# zx80_SD_12_smd_build006_STM32.net
KiCad netlist of a schematic drawn in EAGLE
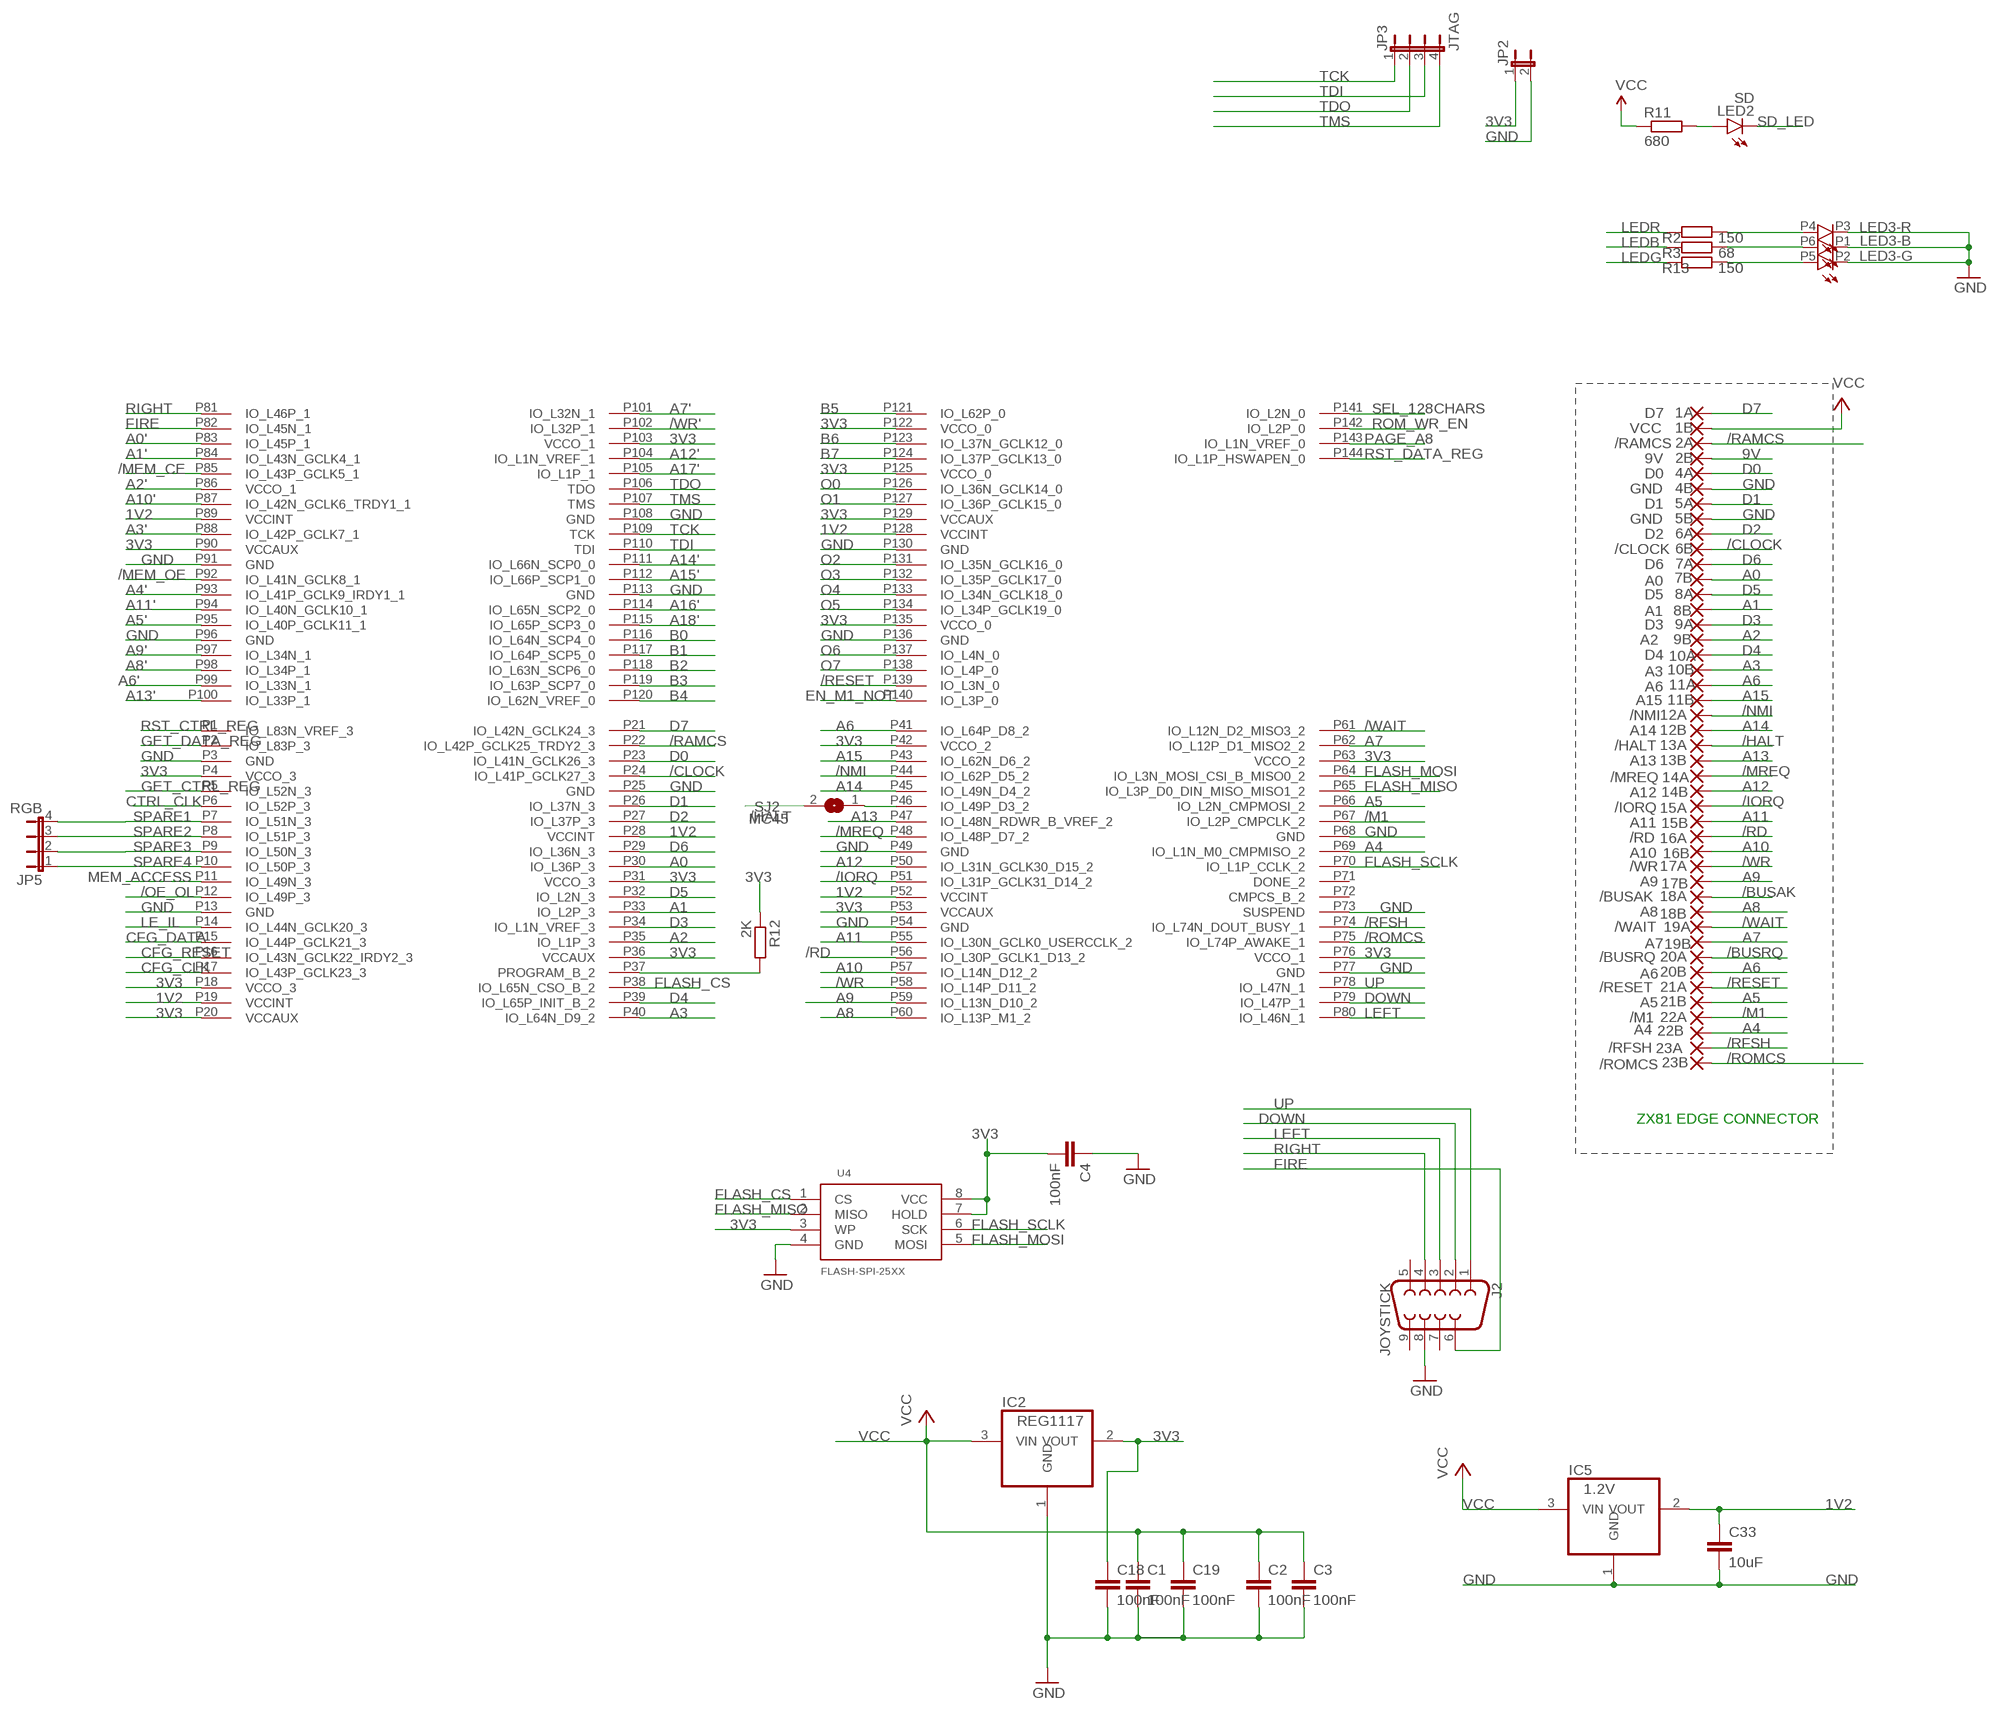
[diagram p0: schematic, sheet 1, part 1 of 2]
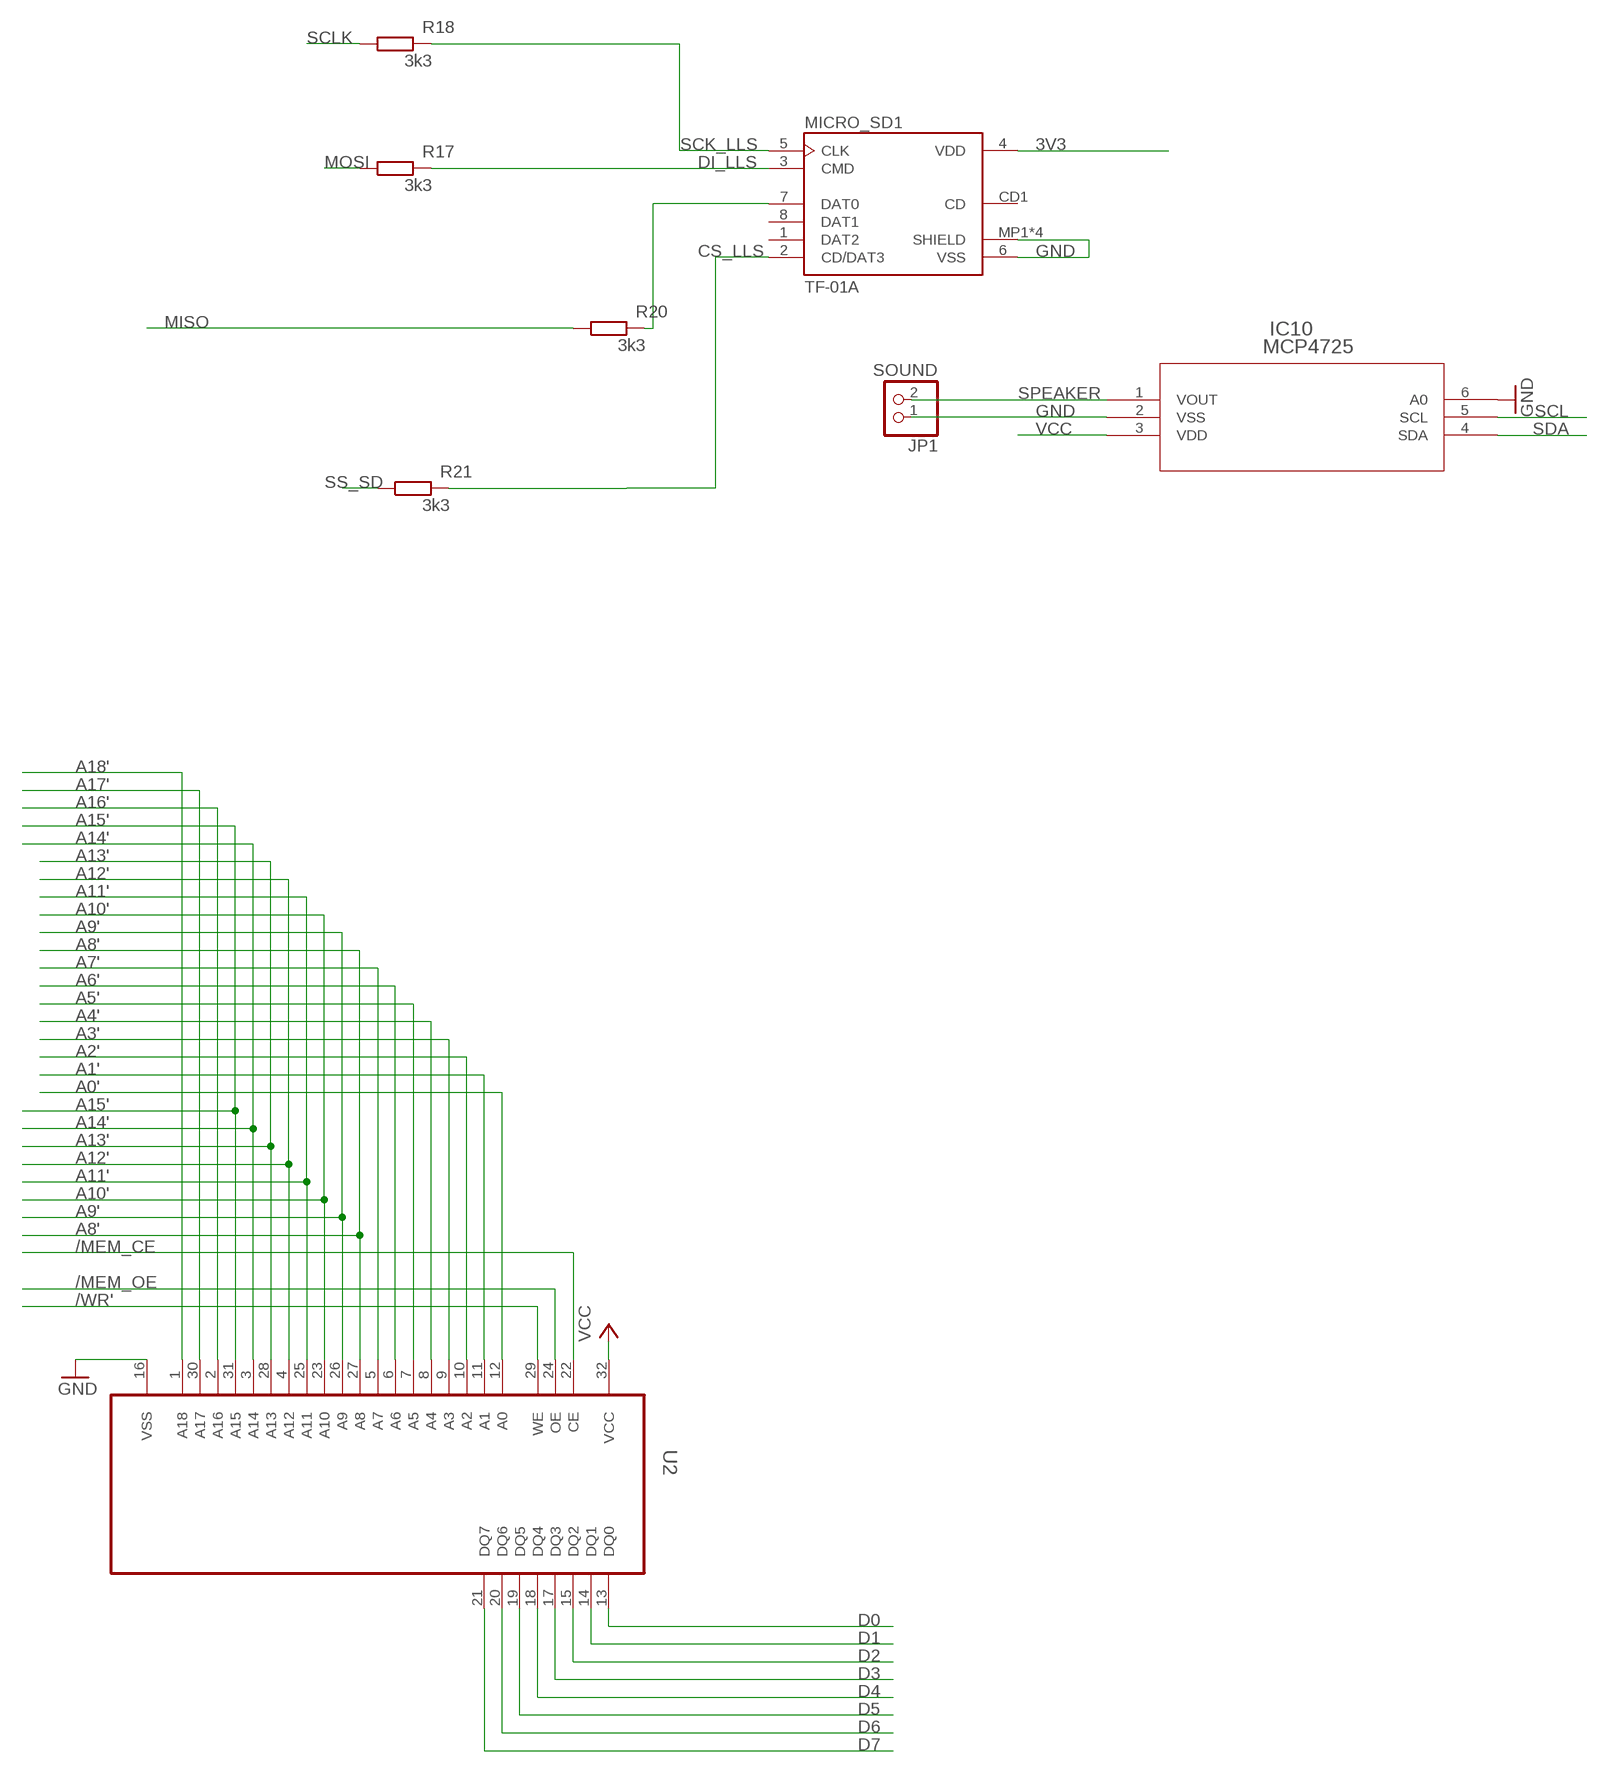
[diagram p1: schematic, sheet 1, part 2 of 2]
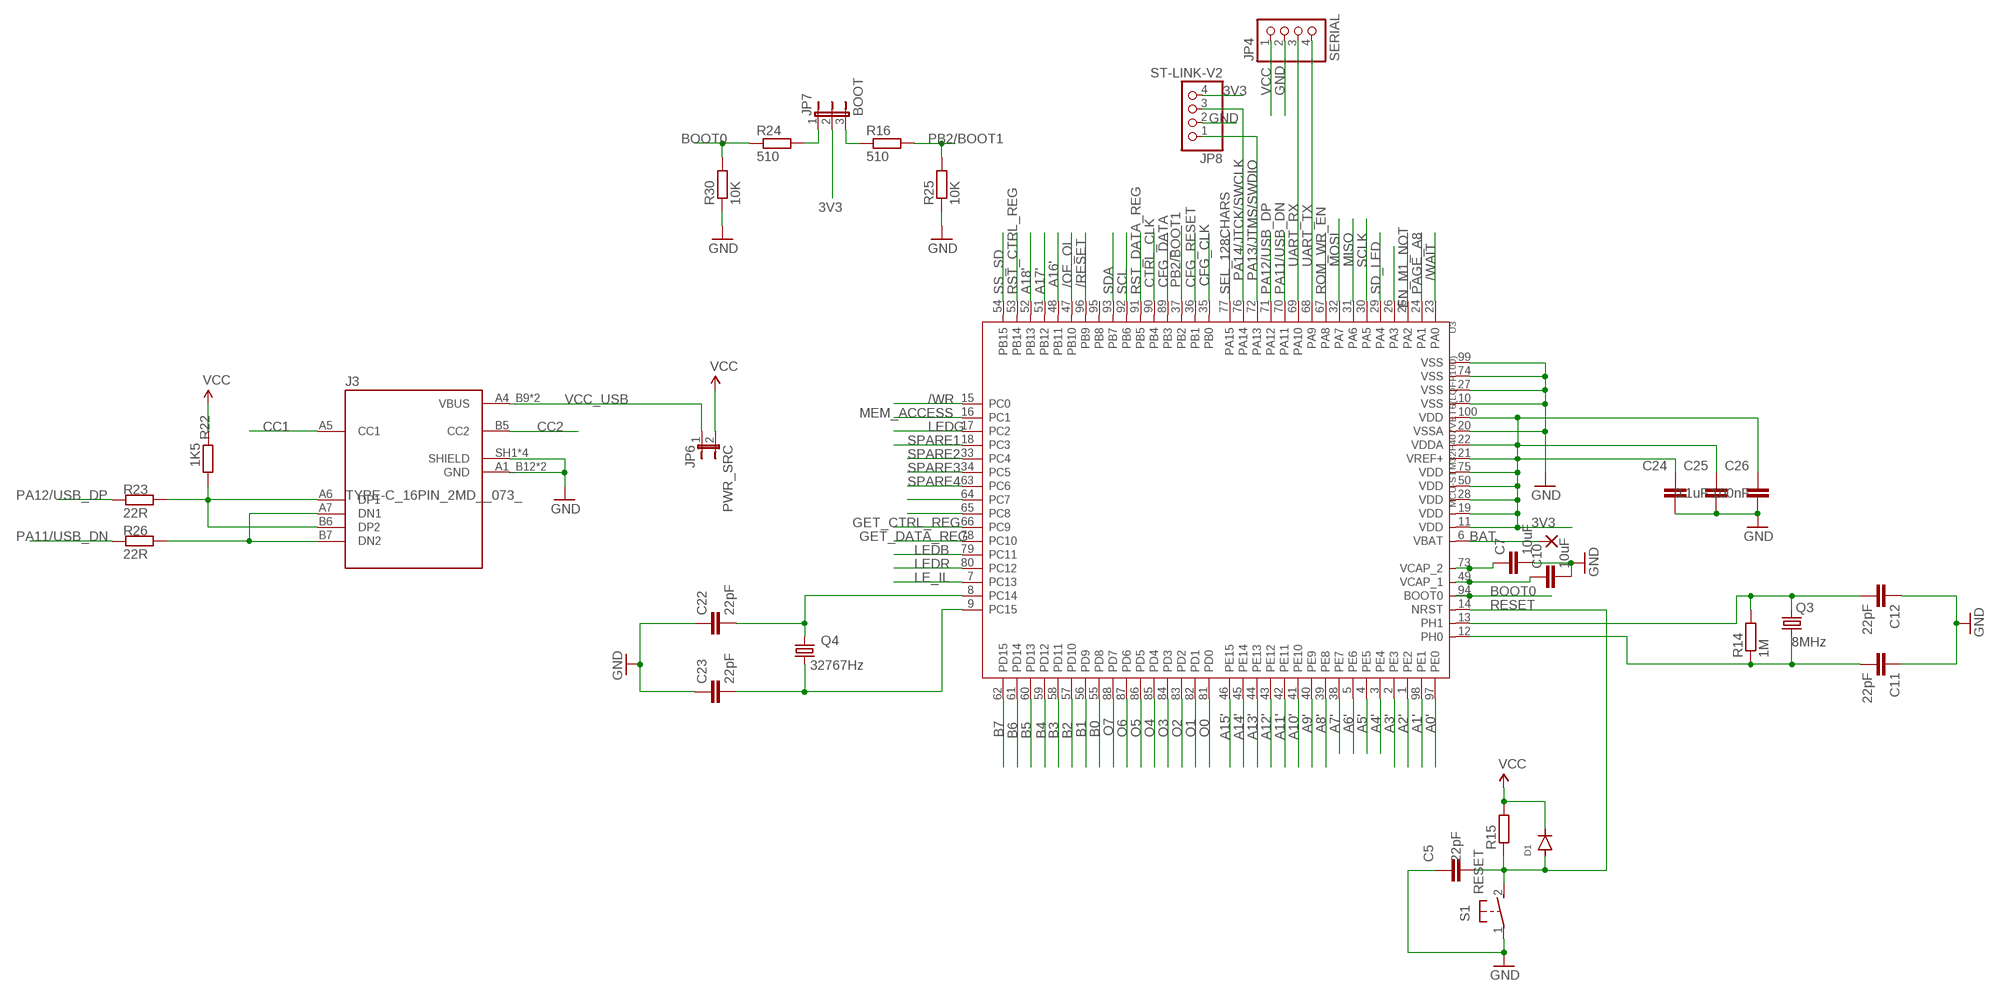
[diagram p2: schematic, sheet 2]

(export (version "E")
  (design (tool "Eeschema 10.0.6"))
  (components
    (comp (ref "BAT")
      (value "1,6/0,8")
      (footprint "eagle-import:1,6_0,8")
      (libsource (lib "eagle-import") (part "1,6/0,8"))
    )
    (comp (ref "C5")
      (value "22pF")
      (footprint "eagle-import:C0603")
      (libsource (lib "eagle-import") (part "rcl_334_C-EUC0603"))
    )
    (comp (ref "C7")
      (value "10uF")
      (footprint "eagle-import:C1206")
      (libsource (lib "eagle-import") (part "rcl_334_C-EUC1206"))
    )
    (comp (ref "C10")
      (value "10uF")
      (footprint "eagle-import:C1206")
      (libsource (lib "eagle-import") (part "rcl_334_C-EUC1206"))
    )
    (comp (ref "C11")
      (value "22pF")
      (footprint "eagle-import:C0603")
      (libsource (lib "eagle-import") (part "rcl_334_C-EUC0603"))
    )
    (comp (ref "C12")
      (value "22pF")
      (footprint "eagle-import:C0603")
      (libsource (lib "eagle-import") (part "rcl_334_C-EUC0603"))
    )
    (comp (ref "C22")
      (value "22pF")
      (footprint "eagle-import:C0603")
      (libsource (lib "eagle-import") (part "rcl_334_C-EUC0603"))
    )
    (comp (ref "C23")
      (value "22pF")
      (footprint "eagle-import:C0603")
      (libsource (lib "eagle-import") (part "rcl_334_C-EUC0603"))
    )
    (comp (ref "C24")
      (value "0.1uF")
      (footprint "eagle-import:C0603")
      (libsource (lib "eagle-import") (part "rcl_334_C-EUC0603"))
    )
    (comp (ref "C25")
      (value "0.1uF")
      (footprint "eagle-import:C0603")
      (libsource (lib "eagle-import") (part "rcl_334_C-EUC0603"))
    )
    (comp (ref "C26")
      (value "100nF")
      (footprint "eagle-import:C0603")
      (libsource (lib "eagle-import") (part "rcl_334_C-EUC0603"))
    )
    (comp (ref "D1")
      (value "DIODE-SOD123")
      (footprint "eagle-import:SOD123")
      (libsource (lib "eagle-import") (part "DIODE-SOD123"))
    )
    (comp (ref "J3")
      (value "TYPE-C_16PIN_2MD__073_")
      (footprint "eagle-import:SHOUHAN_TYPE-C_16PIN_2MD__073_")
      (fields (field (name "MF") "Shouhan") (field (name "MP") "TYPE-C 16PIN 2MD (073)"))
      (libsource (lib "eagle-import") (part "TYPE-C_16PIN_2MD__073_"))
    )
    (comp (ref "JP4")
      (value "SERIAL")
      (footprint "eagle-import:1X04")
      (libsource (lib "eagle-import") (part "PINHD-1X4"))
    )
    (comp (ref "JP6")
      (value "PWR_SRC")
      (footprint "eagle-import:HDRV2W64P254_2X1_300X350X838B")
      (libsource (lib "eagle-import") (part "JP1EJP13D"))
    )
    (comp (ref "JP7")
      (value "BOOT")
      (footprint "eagle-import:HDRV3W64P254_3X1_300X654X838B")
      (libsource (lib "eagle-import") (part "JP2EJP23D"))
    )
    (comp (ref "JP8")
      (value "ST-LINK-V2")
      (footprint "eagle-import:1X04")
      (libsource (lib "eagle-import") (part "PINHD-1X4"))
    )
    (comp (ref "Q3")
      (value "8MHz")
      (footprint "eagle-import:3.2X2.5_KX-7")
      (libsource (lib "eagle-import") (part "KX-7"))
    )
    (comp (ref "Q4")
      (value "32767Hz")
      (footprint "eagle-import:3.2X1.5")
      (libsource (lib "eagle-import") (part "KX-327-NHT"))
    )
    (comp (ref "R14")
      (value "1M")
      (footprint "eagle-import:R0603")
      (libsource (lib "eagle-import") (part "rcl_334_R-EU_R0603"))
    )
    (comp (ref "R15")
      (value "R-EU_R0603")
      (footprint "eagle-import:R0603")
      (libsource (lib "eagle-import") (part "rcl_334_R-EU_R0603"))
    )
    (comp (ref "R16")
      (value "510")
      (footprint "eagle-import:R0603")
      (libsource (lib "eagle-import") (part "rcl_334_R-EU_R0603"))
    )
    (comp (ref "R22")
      (value "1K5")
      (footprint "eagle-import:R0603")
      (libsource (lib "eagle-import") (part "R-EU_R0603"))
    )
    (comp (ref "R23")
      (value "22R")
      (footprint "eagle-import:R0603")
      (libsource (lib "eagle-import") (part "R-EU_R0603"))
    )
    (comp (ref "R24")
      (value "510")
      (footprint "eagle-import:R0603")
      (libsource (lib "eagle-import") (part "rcl_334_R-EU_R0603"))
    )
    (comp (ref "R25")
      (value "10K")
      (footprint "eagle-import:R0603")
      (libsource (lib "eagle-import") (part "rcl_334_R-EU_R0603"))
    )
    (comp (ref "R26")
      (value "22R")
      (footprint "eagle-import:R0603")
      (libsource (lib "eagle-import") (part "R-EU_R0603"))
    )
    (comp (ref "R30")
      (value "10K")
      (footprint "eagle-import:R0603")
      (libsource (lib "eagle-import") (part "rcl_334_R-EU_R0603"))
    )
    (comp (ref "S1")
      (value "RESET")
      (footprint "eagle-import:B3F-31XX")
      (fields (field (name "MPN") "B3F-3100"))
      (libsource (lib "eagle-import") (part "31-XX"))
    )
    (comp (ref "U3")
      (value "MCU-STM32F407VET6(LQFP100)")
      (footprint "eagle-import:LQFP100-0.5-13.8X13.8MM")
      (fields (field (name "MF") "STMicroelectronics") (field (name "MP") "STM32F407VET6"))
      (libsource (lib "eagle-import") (part "MCU-STM32F407VET6(LQFP100)"))
    )
    (comp (ref "1A")
      (value "D7")
      (footprint "eagle-import:EDGEPIN")
      (libsource (lib "eagle-import") (part "SMD2EDGEPIN"))
    )
    (comp (ref "1B")
      (value "VCC")
      (footprint "eagle-import:EDGEPIN")
      (libsource (lib "eagle-import") (part "SMD2EDGEPIN"))
    )
    (comp (ref "2A")
      (value "/RAMCS")
      (footprint "eagle-import:EDGEPIN")
      (libsource (lib "eagle-import") (part "SMD2EDGEPIN"))
    )
    (comp (ref "2B")
      (value "9V")
      (footprint "eagle-import:EDGEPIN")
      (libsource (lib "eagle-import") (part "SMD2EDGEPIN"))
    )
    (comp (ref "4A")
      (value "D0")
      (footprint "eagle-import:EDGEPIN")
      (libsource (lib "eagle-import") (part "SMD2EDGEPIN"))
    )
    (comp (ref "4B")
      (value "GND")
      (footprint "eagle-import:EDGEPIN")
      (libsource (lib "eagle-import") (part "SMD2EDGEPIN"))
    )
    (comp (ref "5A")
      (value "D1")
      (footprint "eagle-import:EDGEPIN")
      (libsource (lib "eagle-import") (part "SMD2EDGEPIN"))
    )
    (comp (ref "5B")
      (value "GND")
      (footprint "eagle-import:EDGEPIN")
      (libsource (lib "eagle-import") (part "SMD2EDGEPIN"))
    )
    (comp (ref "6A")
      (value "D2")
      (footprint "eagle-import:EDGEPIN")
      (libsource (lib "eagle-import") (part "SMD2EDGEPIN"))
    )
    (comp (ref "6B")
      (value "/CLOCK")
      (footprint "eagle-import:EDGEPIN")
      (libsource (lib "eagle-import") (part "SMD2EDGEPIN"))
    )
    (comp (ref "7A")
      (value "D6")
      (footprint "eagle-import:EDGEPIN")
      (libsource (lib "eagle-import") (part "SMD2EDGEPIN"))
    )
    (comp (ref "7B")
      (value "A0")
      (footprint "eagle-import:EDGEPIN")
      (libsource (lib "eagle-import") (part "SMD2EDGEPIN"))
    )
    (comp (ref "8A")
      (value "D5")
      (footprint "eagle-import:EDGEPIN")
      (libsource (lib "eagle-import") (part "SMD2EDGEPIN"))
    )
    (comp (ref "8B")
      (value "A1")
      (footprint "eagle-import:EDGEPIN")
      (libsource (lib "eagle-import") (part "SMD2EDGEPIN"))
    )
    (comp (ref "9A")
      (value "D3")
      (footprint "eagle-import:EDGEPIN")
      (libsource (lib "eagle-import") (part "SMD2EDGEPIN"))
    )
    (comp (ref "9B")
      (value "A2")
      (footprint "eagle-import:EDGEPIN")
      (libsource (lib "eagle-import") (part "SMD2EDGEPIN"))
    )
    (comp (ref "10A")
      (value "D4")
      (footprint "eagle-import:EDGEPIN")
      (libsource (lib "eagle-import") (part "SMD2EDGEPIN"))
    )
    (comp (ref "10B")
      (value "A3")
      (footprint "eagle-import:EDGEPIN")
      (libsource (lib "eagle-import") (part "SMD2EDGEPIN"))
    )
    (comp (ref "11A")
      (value "A6")
      (footprint "eagle-import:EDGEPIN")
      (libsource (lib "eagle-import") (part "SMD2EDGEPIN"))
    )
    (comp (ref "11B")
      (value "A15")
      (footprint "eagle-import:EDGEPIN")
      (libsource (lib "eagle-import") (part "SMD2EDGEPIN"))
    )
    (comp (ref "12A")
      (value "/NMI")
      (footprint "eagle-import:EDGEPIN")
      (libsource (lib "eagle-import") (part "SMD2EDGEPIN"))
    )
    (comp (ref "12B")
      (value "A14")
      (footprint "eagle-import:EDGEPIN")
      (libsource (lib "eagle-import") (part "SMD2EDGEPIN"))
    )
    (comp (ref "13A")
      (value "/HALT")
      (footprint "eagle-import:EDGEPIN")
      (libsource (lib "eagle-import") (part "SMD2EDGEPIN"))
    )
    (comp (ref "13B")
      (value "A13")
      (footprint "eagle-import:EDGEPIN")
      (libsource (lib "eagle-import") (part "SMD2EDGEPIN"))
    )
    (comp (ref "14A")
      (value "/MREQ")
      (footprint "eagle-import:EDGEPIN")
      (libsource (lib "eagle-import") (part "SMD2EDGEPIN"))
    )
    (comp (ref "14B")
      (value "A12")
      (footprint "eagle-import:EDGEPIN")
      (libsource (lib "eagle-import") (part "SMD2EDGEPIN"))
    )
    (comp (ref "15A")
      (value "/IORQ")
      (footprint "eagle-import:EDGEPIN")
      (libsource (lib "eagle-import") (part "SMD2EDGEPIN"))
    )
    (comp (ref "15B")
      (value "A11")
      (footprint "eagle-import:EDGEPIN")
      (libsource (lib "eagle-import") (part "SMD2EDGEPIN"))
    )
    (comp (ref "16A")
      (value "/RD")
      (footprint "eagle-import:EDGEPIN")
      (libsource (lib "eagle-import") (part "SMD2EDGEPIN"))
    )
    (comp (ref "16B")
      (value "A10")
      (footprint "eagle-import:EDGEPIN")
      (libsource (lib "eagle-import") (part "SMD2EDGEPIN"))
    )
    (comp (ref "17A")
      (value "/WR")
      (footprint "eagle-import:EDGEPIN")
      (libsource (lib "eagle-import") (part "SMD2EDGEPIN"))
    )
    (comp (ref "17B")
      (value "A9")
      (footprint "eagle-import:EDGEPIN")
      (libsource (lib "eagle-import") (part "SMD2EDGEPIN"))
    )
    (comp (ref "18A")
      (value "/BUSAK")
      (footprint "eagle-import:EDGEPIN")
      (libsource (lib "eagle-import") (part "SMD2EDGEPIN"))
    )
    (comp (ref "18B")
      (value "A8")
      (footprint "eagle-import:EDGEPIN")
      (libsource (lib "eagle-import") (part "SMD2EDGEPIN"))
    )
    (comp (ref "19A")
      (value "/WAIT")
      (footprint "eagle-import:EDGEPIN")
      (libsource (lib "eagle-import") (part "SMD2EDGEPIN"))
    )
    (comp (ref "19B")
      (value "A7")
      (footprint "eagle-import:EDGEPIN")
      (libsource (lib "eagle-import") (part "SMD2EDGEPIN"))
    )
    (comp (ref "20A")
      (value "/BUSRQ")
      (footprint "eagle-import:EDGEPIN")
      (libsource (lib "eagle-import") (part "SMD2EDGEPIN"))
    )
    (comp (ref "20B")
      (value "A6")
      (footprint "eagle-import:EDGEPIN")
      (libsource (lib "eagle-import") (part "SMD2EDGEPIN"))
    )
    (comp (ref "21A")
      (value "/RESET")
      (footprint "eagle-import:EDGEPIN")
      (libsource (lib "eagle-import") (part "SMD2EDGEPIN"))
    )
    (comp (ref "21B")
      (value "A5")
      (footprint "eagle-import:EDGEPIN")
      (libsource (lib "eagle-import") (part "SMD2EDGEPIN"))
    )
    (comp (ref "22A")
      (value "/M1")
      (footprint "eagle-import:EDGEPIN")
      (libsource (lib "eagle-import") (part "SMD2EDGEPIN"))
    )
    (comp (ref "22B")
      (value "A4")
      (footprint "eagle-import:EDGEPIN")
      (libsource (lib "eagle-import") (part "SMD2EDGEPIN"))
    )
    (comp (ref "23A")
      (value "/RFSH")
      (footprint "eagle-import:EDGEPIN")
      (libsource (lib "eagle-import") (part "SMD2EDGEPIN"))
    )
    (comp (ref "23B")
      (value "/ROMCS")
      (footprint "eagle-import:EDGEPIN")
      (libsource (lib "eagle-import") (part "SMD2EDGEPIN"))
    )
    (comp (ref "C1")
      (value "100nF")
      (footprint "eagle-import:C0603")
      (libsource (lib "eagle-import") (part "rcl_334_C-EUC0603"))
    )
    (comp (ref "C2")
      (value "100nF")
      (footprint "eagle-import:C0603")
      (libsource (lib "eagle-import") (part "rcl_334_C-EUC0603"))
    )
    (comp (ref "C3")
      (value "100nF")
      (footprint "eagle-import:C0603")
      (libsource (lib "eagle-import") (part "rcl_334_C-EUC0603"))
    )
    (comp (ref "C4")
      (value "100nF")
      (footprint "eagle-import:C0603K")
      (libsource (lib "eagle-import") (part "C-EUC0603K"))
    )
    (comp (ref "C18")
      (value "100nF")
      (footprint "eagle-import:C0603")
      (libsource (lib "eagle-import") (part "rcl_334_C-EUC0603"))
    )
    (comp (ref "C19")
      (value "100nF")
      (footprint "eagle-import:C0603")
      (libsource (lib "eagle-import") (part "rcl_334_C-EUC0603"))
    )
    (comp (ref "C33")
      (value "10uF")
      (footprint "eagle-import:C0603K")
      (libsource (lib "eagle-import") (part "C-EUC0603K"))
    )
    (comp (ref "IC2")
      (value "REG1117")
      (footprint "eagle-import:SOT223")
      (libsource (lib "eagle-import") (part "burr-brown_41243815_REG1117"))
    )
    (comp (ref "IC5")
      (value "1.2V")
      (footprint "eagle-import:SOT223")
      (fields (field (name "MPN") "REG1117"))
      (libsource (lib "eagle-import") (part "REG1117"))
    )
    (comp (ref "IC10")
      (value "MCP4725")
      (footprint "eagle-import:SOT-23-6_MC")
      (fields (field (name "MF") "Microchip") (field (name "MP") "MCP4725A2T-E/CH"))
      (libsource (lib "eagle-import") (part "MCP4725A2T-E/CH"))
    )
    (comp (ref "J2")
      (value "JOYSTICK")
      (footprint "eagle-import:DB9_MALE")
      (libsource (lib "eagle-import") (part "DB9MALE"))
    )
    (comp (ref "JP1")
      (value "SOUND")
      (footprint "eagle-import:1X02")
      (libsource (lib "eagle-import") (part "PINHD-1X2"))
    )
    (comp (ref "JP2")
      (value "JP1E")
      (footprint "eagle-import:JP1")
      (libsource (lib "eagle-import") (part "JP1E"))
    )
    (comp (ref "JP3")
      (value "JTAG")
      (footprint "eagle-import:JP4")
      (libsource (lib "eagle-import") (part "JP4E"))
    )
    (comp (ref "JP5")
      (value "RGB")
      (footprint "eagle-import:JP4")
      (libsource (lib "eagle-import") (part "JP4E"))
    )
    (comp (ref "LED2")
      (value "SD")
      (footprint "eagle-import:CHIPLED_0603")
      (libsource (lib "eagle-import") (part "LEDCHIPLED_0603"))
    )
    (comp (ref "LED3")
      (value "STATUS")
      (footprint "eagle-import:3535-PLCC6")
      (libsource (lib "eagle-import") (part "3535RGB3535RGB"))
    )
    (comp (ref "MICRO_SD1")
      (value "TF-01A")
      (footprint "eagle-import:TF-01A")
      (fields (field (name "MF") "HRO Electronics Co., Ltd."))
      (libsource (lib "eagle-import") (part "TF-01A"))
    )
    (comp (ref "R2")
      (value "150")
      (footprint "eagle-import:R0603")
      (libsource (lib "eagle-import") (part "rcl_334_R-EU_R0603"))
    )
    (comp (ref "R3")
      (value "68")
      (footprint "eagle-import:R0603")
      (libsource (lib "eagle-import") (part "rcl_334_R-EU_R0603"))
    )
    (comp (ref "R11")
      (value "680")
      (footprint "eagle-import:R0603")
      (libsource (lib "eagle-import") (part "R-EU_R0603"))
    )
    (comp (ref "R12")
      (value "2K")
      (footprint "eagle-import:R0603")
      (libsource (lib "eagle-import") (part "rcl_334_R-EU_R0603"))
    )
    (comp (ref "R13")
      (value "150")
      (footprint "eagle-import:R0603")
      (libsource (lib "eagle-import") (part "rcl_334_R-EU_R0603"))
    )
    (comp (ref "R17")
      (value "3k3")
      (footprint "eagle-import:R0603")
      (libsource (lib "eagle-import") (part "R-EU_R0603"))
    )
    (comp (ref "R18")
      (value "3k3")
      (footprint "eagle-import:R0603")
      (libsource (lib "eagle-import") (part "R-EU_R0603"))
    )
    (comp (ref "R20")
      (value "3k3")
      (footprint "eagle-import:R0603")
      (libsource (lib "eagle-import") (part "R-EU_R0603"))
    )
    (comp (ref "R21")
      (value "3k3")
      (footprint "eagle-import:R0603")
      (libsource (lib "eagle-import") (part "R-EU_R0603"))
    )
    (comp (ref "SJ2")
      (value "MC45")
      (footprint "eagle-import:SJ")
      (libsource (lib "eagle-import") (part "SJ"))
    )
    (comp (ref "U$1")
      (value "XC6SLX9-2TQG144C")
      (footprint "eagle-import:TQ144")
      (fields (field (name "MF") "Xilinx Inc."))
      (libsource (lib "eagle-import") (part "XC6SLX9-2TQG144C"))
    )
    (comp (ref "U2")
      (value "AS6C4008")
      (footprint "eagle-import:SOP32-5")
      (libsource (lib "eagle-import") (part "AS6C4008-55SINSOP5"))
    )
    (comp (ref "U4")
      (value "FLASH-SPI-25XX")
      (footprint "eagle-import:SO08-EIAJ")
      (libsource (lib "eagle-import") (part "FLASH-SPI-25XXSMD1"))
    )
  )
  (nets
    (net (code "1") (name "1V2") (class "Default")
      (node (ref "C33") (pin "1") (pinfunction "1_1") (pintype "passive"))
      (node (ref "IC5") (pin "2") (pinfunction "VOUT_2") (pintype "output"))
      (node (ref "U$1") (pin "P128") (pinfunction "VCCINT_P128") (pintype "bidirectional"))
      (node (ref "U$1") (pin "P19") (pinfunction "VCCINT_P19") (pintype "bidirectional"))
      (node (ref "U$1") (pin "P28") (pinfunction "VCCINT_P28") (pintype "bidirectional"))
      (node (ref "U$1") (pin "P52") (pinfunction "VCCINT_P52") (pintype "bidirectional"))
      (node (ref "U$1") (pin "P89") (pinfunction "VCCINT_P89") (pintype "bidirectional"))
    )
    (net (code "2") (name "3V3") (class "Default")
      (node (ref "C18") (pin "1") (pinfunction "1_1") (pintype "passive"))
      (node (ref "C24") (pin "1") (pinfunction "1_1") (pintype "passive"))
      (node (ref "C25") (pin "1") (pinfunction "1_1") (pintype "passive"))
      (node (ref "C26") (pin "1") (pinfunction "1_1") (pintype "passive"))
      (node (ref "C4") (pin "2") (pinfunction "2_2") (pintype "passive"))
      (node (ref "IC2") (pin "2") (pinfunction "VOUT_2") (pintype "output"))
      (node (ref "JP2") (pin "1") (pinfunction "1_1") (pintype "passive"))
      (node (ref "JP7") (pin "2") (pinfunction "2_2") (pintype "passive"))
      (node (ref "JP8") (pin "4") (pinfunction "4_4") (pintype "passive"))
      (node (ref "MICRO_SD1") (pin "4") (pinfunction "VDD_4") (pintype "power_in"))
      (node (ref "R12") (pin "1") (pinfunction "1_1") (pintype "passive"))
      (node (ref "U$1") (pin "P103") (pinfunction "VCCO_1_P103") (pintype "bidirectional"))
      (node (ref "U$1") (pin "P122") (pinfunction "VCCO_0_P122") (pintype "bidirectional"))
      (node (ref "U$1") (pin "P125") (pinfunction "VCCO_0_P125") (pintype "bidirectional"))
      (node (ref "U$1") (pin "P129") (pinfunction "VCCAUX_P129") (pintype "bidirectional"))
      (node (ref "U$1") (pin "P135") (pinfunction "VCCO_0_P135") (pintype "bidirectional"))
      (node (ref "U$1") (pin "P18") (pinfunction "VCCO_3_P18") (pintype "bidirectional"))
      (node (ref "U$1") (pin "P20") (pinfunction "VCCAUX_P20") (pintype "bidirectional"))
      (node (ref "U$1") (pin "P31") (pinfunction "VCCO_3_P31") (pintype "bidirectional"))
      (node (ref "U$1") (pin "P36") (pinfunction "VCCAUX_P36") (pintype "bidirectional"))
      (node (ref "U$1") (pin "P4") (pinfunction "VCCO_3_P4") (pintype "bidirectional"))
      (node (ref "U$1") (pin "P42") (pinfunction "VCCO_2_P42") (pintype "bidirectional"))
      (node (ref "U$1") (pin "P53") (pinfunction "VCCAUX_P53") (pintype "bidirectional"))
      (node (ref "U$1") (pin "P63") (pinfunction "VCCO_2_P63") (pintype "bidirectional"))
      (node (ref "U$1") (pin "P76") (pinfunction "VCCO_1_P76") (pintype "bidirectional"))
      (node (ref "U$1") (pin "P90") (pinfunction "VCCAUX_P90") (pintype "bidirectional"))
      (node (ref "U3") (pin "100") (pinfunction "VDD_100") (pintype "bidirectional"))
      (node (ref "U3") (pin "11") (pinfunction "VDD_11") (pintype "bidirectional"))
      (node (ref "U3") (pin "19") (pinfunction "VDD_19") (pintype "bidirectional"))
      (node (ref "U3") (pin "21") (pinfunction "VREF+_21") (pintype "bidirectional"))
      (node (ref "U3") (pin "22") (pinfunction "VDDA_22") (pintype "bidirectional"))
      (node (ref "U3") (pin "28") (pinfunction "VDD_28") (pintype "bidirectional"))
      (node (ref "U3") (pin "50") (pinfunction "VDD_50") (pintype "bidirectional"))
      (node (ref "U3") (pin "75") (pinfunction "VDD_75") (pintype "bidirectional"))
      (node (ref "U4") (pin "3") (pinfunction "WP_3") (pintype "bidirectional"))
      (node (ref "U4") (pin "7") (pinfunction "HOLD_7") (pintype "bidirectional"))
      (node (ref "U4") (pin "8") (pinfunction "VCC_8") (pintype "bidirectional"))
    )
    (net (code "3") (name "9V") (class "Default")
      (node (ref "2B") (pin "1") (pinfunction "P_1") (pintype "passive"))
    )
    (net (code "4") (name "A0") (class "Default")
      (node (ref "7B") (pin "1") (pinfunction "P_1") (pintype "passive"))
      (node (ref "U$1") (pin "P30") (pinfunction "IO_L36P_3_P30") (pintype "bidirectional"))
    )
    (net (code "5") (name "A0'") (class "Default")
      (node (ref "U$1") (pin "P83") (pinfunction "IO_L45P_1_P83") (pintype "bidirectional"))
      (node (ref "U2") (pin "12") (pinfunction "A0_12") (pintype "input"))
      (node (ref "U3") (pin "97") (pinfunction "PE0_97") (pintype "bidirectional"))
    )
    (net (code "6") (name "A1") (class "Default")
      (node (ref "8B") (pin "1") (pinfunction "P_1") (pintype "passive"))
      (node (ref "U$1") (pin "P33") (pinfunction "IO_L2P_3_P33") (pintype "bidirectional"))
    )
    (net (code "7") (name "A1'") (class "Default")
      (node (ref "U$1") (pin "P84") (pinfunction "IO_L43N_GCLK4_1_P84") (pintype "bidirectional"))
      (node (ref "U2") (pin "11") (pinfunction "A1_11") (pintype "input"))
      (node (ref "U3") (pin "98") (pinfunction "PE1_98") (pintype "bidirectional"))
    )
    (net (code "8") (name "A2") (class "Default")
      (node (ref "9B") (pin "1") (pinfunction "P_1") (pintype "passive"))
      (node (ref "U$1") (pin "P35") (pinfunction "IO_L1P_3_P35") (pintype "bidirectional"))
    )
    (net (code "9") (name "A2'") (class "Default")
      (node (ref "U$1") (pin "P86") (pinfunction "VCCO_1_P86") (pintype "bidirectional"))
      (node (ref "U2") (pin "10") (pinfunction "A2_10") (pintype "input"))
      (node (ref "U3") (pin "1") (pinfunction "PE2_1") (pintype "bidirectional"))
    )
    (net (code "10") (name "A3") (class "Default")
      (node (ref "10B") (pin "1") (pinfunction "P_1") (pintype "passive"))
      (node (ref "U$1") (pin "P40") (pinfunction "IO_L64N_D9_2_P40") (pintype "bidirectional"))
    )
    (net (code "11") (name "A3'") (class "Default")
      (node (ref "U$1") (pin "P88") (pinfunction "IO_L42P_GCLK7_1_P88") (pintype "bidirectional"))
      (node (ref "U2") (pin "9") (pinfunction "A3_9") (pintype "input"))
      (node (ref "U3") (pin "2") (pinfunction "PE3_2") (pintype "bidirectional"))
    )
    (net (code "12") (name "A4") (class "Default")
      (node (ref "22B") (pin "1") (pinfunction "P_1") (pintype "passive"))
      (node (ref "U$1") (pin "P69") (pinfunction "IO_L1N_M0_CMPMISO_2_P69") (pintype "bidirectional"))
    )
    (net (code "13") (name "A4'") (class "Default")
      (node (ref "U$1") (pin "P93") (pinfunction "IO_L41P_GCLK9_IRDY1_1_P93") (pintype "bidirectional"))
      (node (ref "U2") (pin "8") (pinfunction "A4_8") (pintype "input"))
      (node (ref "U3") (pin "3") (pinfunction "PE4_3") (pintype "bidirectional"))
    )
    (net (code "14") (name "A5") (class "Default")
      (node (ref "21B") (pin "1") (pinfunction "P_1") (pintype "passive"))
      (node (ref "U$1") (pin "P66") (pinfunction "IO_L2N_CMPMOSI_2_P66") (pintype "bidirectional"))
    )
    (net (code "15") (name "A5'") (class "Default")
      (node (ref "U$1") (pin "P95") (pinfunction "IO_L40P_GCLK11_1_P95") (pintype "bidirectional"))
      (node (ref "U2") (pin "7") (pinfunction "A5_7") (pintype "input"))
      (node (ref "U3") (pin "4") (pinfunction "PE5_4") (pintype "bidirectional"))
    )
    (net (code "16") (name "A6") (class "Default")
      (node (ref "11A") (pin "1") (pinfunction "P_1") (pintype "passive"))
      (node (ref "20B") (pin "1") (pinfunction "P_1") (pintype "passive"))
      (node (ref "U$1") (pin "P41") (pinfunction "IO_L64P_D8_2_P41") (pintype "bidirectional"))
    )
    (net (code "17") (name "A6'") (class "Default")
      (node (ref "U$1") (pin "P99") (pinfunction "IO_L33N_1_P99") (pintype "bidirectional"))
      (node (ref "U2") (pin "6") (pinfunction "A6_6") (pintype "input"))
      (node (ref "U3") (pin "5") (pinfunction "PE6_5") (pintype "bidirectional"))
    )
    (net (code "18") (name "A7") (class "Default")
      (node (ref "19B") (pin "1") (pinfunction "P_1") (pintype "passive"))
      (node (ref "U$1") (pin "P62") (pinfunction "IO_L12P_D1_MISO2_2_P62") (pintype "bidirectional"))
    )
    (net (code "19") (name "A7'") (class "Default")
      (node (ref "U$1") (pin "P101") (pinfunction "IO_L32N_1_P101") (pintype "bidirectional"))
      (node (ref "U2") (pin "5") (pinfunction "A7_5") (pintype "input"))
      (node (ref "U3") (pin "38") (pinfunction "PE7_38") (pintype "bidirectional"))
    )
    (net (code "20") (name "A8") (class "Default")
      (node (ref "18B") (pin "1") (pinfunction "P_1") (pintype "passive"))
      (node (ref "U$1") (pin "P60") (pinfunction "IO_L13P_M1_2_P60") (pintype "bidirectional"))
    )
    (net (code "21") (name "A8'") (class "Default")
      (node (ref "U$1") (pin "P98") (pinfunction "IO_L34P_1_P98") (pintype "bidirectional"))
      (node (ref "U2") (pin "27") (pinfunction "A8_27") (pintype "input"))
      (node (ref "U3") (pin "39") (pinfunction "PE8_39") (pintype "bidirectional"))
    )
    (net (code "22") (name "A9") (class "Default")
      (node (ref "17B") (pin "1") (pinfunction "P_1") (pintype "passive"))
      (node (ref "U$1") (pin "P59") (pinfunction "IO_L13N_D10_2_P59") (pintype "bidirectional"))
    )
    (net (code "23") (name "A9'") (class "Default")
      (node (ref "U$1") (pin "P97") (pinfunction "IO_L34N_1_P97") (pintype "bidirectional"))
      (node (ref "U2") (pin "26") (pinfunction "A9_26") (pintype "input"))
      (node (ref "U3") (pin "40") (pinfunction "PE9_40") (pintype "bidirectional"))
    )
    (net (code "24") (name "A10") (class "Default")
      (node (ref "16B") (pin "1") (pinfunction "P_1") (pintype "passive"))
      (node (ref "U$1") (pin "P57") (pinfunction "IO_L14N_D12_2_P57") (pintype "bidirectional"))
    )
    (net (code "25") (name "A10'") (class "Default")
      (node (ref "U$1") (pin "P87") (pinfunction "IO_L42N_GCLK6_TRDY1_1_P87") (pintype "bidirectional"))
      (node (ref "U2") (pin "23") (pinfunction "A10_23") (pintype "input"))
      (node (ref "U3") (pin "41") (pinfunction "PE10_41") (pintype "bidirectional"))
    )
    (net (code "26") (name "A11") (class "Default")
      (node (ref "15B") (pin "1") (pinfunction "P_1") (pintype "passive"))
      (node (ref "U$1") (pin "P55") (pinfunction "IO_L30N_GCLK0_USERCCLK_2_P55") (pintype "bidirectional"))
    )
    (net (code "27") (name "A11'") (class "Default")
      (node (ref "U$1") (pin "P94") (pinfunction "IO_L40N_GCLK10_1_P94") (pintype "bidirectional"))
      (node (ref "U2") (pin "25") (pinfunction "A11_25") (pintype "input"))
      (node (ref "U3") (pin "42") (pinfunction "PE11_42") (pintype "bidirectional"))
    )
    (net (code "28") (name "A12") (class "Default")
      (node (ref "14B") (pin "1") (pinfunction "P_1") (pintype "passive"))
      (node (ref "U$1") (pin "P50") (pinfunction "IO_L31N_GCLK30_D15_2_P50") (pintype "bidirectional"))
    )
    (net (code "29") (name "A12'") (class "Default")
      (node (ref "U$1") (pin "P104") (pinfunction "IO_L1N_VREF_1_P104") (pintype "bidirectional"))
      (node (ref "U2") (pin "4") (pinfunction "A12_4") (pintype "input"))
      (node (ref "U3") (pin "43") (pinfunction "PE12_43") (pintype "bidirectional"))
    )
    (net (code "30") (name "A13") (class "Default")
      (node (ref "13B") (pin "1") (pinfunction "P_1") (pintype "passive"))
      (node (ref "U$1") (pin "P47") (pinfunction "IO_L48N_RDWR_B_VREF_2_P47") (pintype "bidirectional"))
    )
    (net (code "31") (name "A13'") (class "Default")
      (node (ref "U$1") (pin "P100") (pinfunction "IO_L33P_1_P100") (pintype "bidirectional"))
      (node (ref "U2") (pin "28") (pinfunction "A13_28") (pintype "input"))
      (node (ref "U3") (pin "44") (pinfunction "PE13_44") (pintype "bidirectional"))
    )
    (net (code "32") (name "A14") (class "Default")
      (node (ref "12B") (pin "1") (pinfunction "P_1") (pintype "passive"))
      (node (ref "U$1") (pin "P45") (pinfunction "IO_L49N_D4_2_P45") (pintype "bidirectional"))
    )
    (net (code "33") (name "A14'") (class "Default")
      (node (ref "U$1") (pin "P111") (pinfunction "IO_L66N_SCP0_0_P111") (pintype "bidirectional"))
      (node (ref "U2") (pin "3") (pinfunction "A14_3") (pintype "input"))
      (node (ref "U3") (pin "45") (pinfunction "PE14_45") (pintype "bidirectional"))
    )
    (net (code "34") (name "A15") (class "Default")
      (node (ref "11B") (pin "1") (pinfunction "P_1") (pintype "passive"))
      (node (ref "U$1") (pin "P43") (pinfunction "IO_L62N_D6_2_P43") (pintype "bidirectional"))
    )
    (net (code "35") (name "A15'") (class "Default")
      (node (ref "U$1") (pin "P112") (pinfunction "IO_L66P_SCP1_0_P112") (pintype "bidirectional"))
      (node (ref "U2") (pin "31") (pinfunction "A15_31") (pintype "input"))
      (node (ref "U3") (pin "46") (pinfunction "PE15_46") (pintype "bidirectional"))
    )
    (net (code "36") (name "A16'") (class "Default")
      (node (ref "U$1") (pin "P114") (pinfunction "IO_L65N_SCP2_0_P114") (pintype "bidirectional"))
      (node (ref "U2") (pin "2") (pinfunction "A16_2") (pintype "input"))
      (node (ref "U3") (pin "48") (pinfunction "PB11_48") (pintype "bidirectional"))
    )
    (net (code "37") (name "A17'") (class "Default")
      (node (ref "U$1") (pin "P105") (pinfunction "IO_L1P_1_P105") (pintype "bidirectional"))
      (node (ref "U2") (pin "30") (pinfunction "A17_30") (pintype "input"))
      (node (ref "U3") (pin "51") (pinfunction "PB12_51") (pintype "bidirectional"))
    )
    (net (code "38") (name "A18'") (class "Default")
      (node (ref "U$1") (pin "P115") (pinfunction "IO_L65P_SCP3_0_P115") (pintype "bidirectional"))
      (node (ref "U2") (pin "1") (pinfunction "A18_1") (pintype "input"))
      (node (ref "U3") (pin "52") (pinfunction "PB13_52") (pintype "bidirectional"))
    )
    (net (code "39") (name "B0") (class "Default")
      (node (ref "U$1") (pin "P116") (pinfunction "IO_L64N_SCP4_0_P116") (pintype "bidirectional"))
      (node (ref "U3") (pin "55") (pinfunction "PD8_55") (pintype "bidirectional"))
    )
    (net (code "40") (name "B1") (class "Default")
      (node (ref "U$1") (pin "P117") (pinfunction "IO_L64P_SCP5_0_P117") (pintype "bidirectional"))
      (node (ref "U3") (pin "56") (pinfunction "PD9_56") (pintype "bidirectional"))
    )
    (net (code "41") (name "B2") (class "Default")
      (node (ref "U$1") (pin "P118") (pinfunction "IO_L63N_SCP6_0_P118") (pintype "bidirectional"))
      (node (ref "U3") (pin "57") (pinfunction "PD10_57") (pintype "bidirectional"))
    )
    (net (code "42") (name "B3") (class "Default")
      (node (ref "U$1") (pin "P119") (pinfunction "IO_L63P_SCP7_0_P119") (pintype "bidirectional"))
      (node (ref "U3") (pin "58") (pinfunction "PD11_58") (pintype "bidirectional"))
    )
    (net (code "43") (name "B4") (class "Default")
      (node (ref "U$1") (pin "P120") (pinfunction "IO_L62N_VREF_0_P120") (pintype "bidirectional"))
      (node (ref "U3") (pin "59") (pinfunction "PD12_59") (pintype "bidirectional"))
    )
    (net (code "44") (name "B5") (class "Default")
      (node (ref "U$1") (pin "P121") (pinfunction "IO_L62P_0_P121") (pintype "bidirectional"))
      (node (ref "U3") (pin "60") (pinfunction "PD13_60") (pintype "bidirectional"))
    )
    (net (code "45") (name "B6") (class "Default")
      (node (ref "U$1") (pin "P123") (pinfunction "IO_L37N_GCLK12_0_P123") (pintype "bidirectional"))
      (node (ref "U3") (pin "61") (pinfunction "PD14_61") (pintype "bidirectional"))
    )
    (net (code "46") (name "B7") (class "Default")
      (node (ref "U$1") (pin "P124") (pinfunction "IO_L37P_GCLK13_0_P124") (pintype "bidirectional"))
      (node (ref "U3") (pin "62") (pinfunction "PD15_62") (pintype "bidirectional"))
    )
    (net (code "47") (name "BAT") (class "Default")
      (node (ref "BAT") (pin "1") (pinfunction "P_1") (pintype "passive"))
      (node (ref "U3") (pin "6") (pinfunction "VBAT_6") (pintype "bidirectional"))
    )
    (net (code "48") (name "BOOT0") (class "Default")
      (node (ref "R24") (pin "1") (pinfunction "1_1") (pintype "passive"))
      (node (ref "R30") (pin "2") (pinfunction "2_2") (pintype "passive"))
      (node (ref "U3") (pin "94") (pinfunction "BOOT0_94") (pintype "bidirectional"))
    )
    (net (code "49") (name "CC1") (class "Default")
      (node (ref "J3") (pin "A5") (pinfunction "CC1_A5") (pintype "bidirectional"))
    )
    (net (code "50") (name "CC2") (class "Default")
      (node (ref "J3") (pin "B5") (pinfunction "CC2_B5") (pintype "bidirectional"))
    )
    (net (code "51") (name "CFG_CLK") (class "Default")
      (node (ref "U$1") (pin "P17") (pinfunction "IO_L43P_GCLK23_3_P17") (pintype "bidirectional"))
      (node (ref "U3") (pin "35") (pinfunction "PB0_35") (pintype "bidirectional"))
    )
    (net (code "52") (name "CFG_DATA") (class "Default")
      (node (ref "U$1") (pin "P15") (pinfunction "IO_L44P_GCLK21_3_P15") (pintype "bidirectional"))
      (node (ref "U3") (pin "89") (pinfunction "PB3_89") (pintype "bidirectional"))
    )
    (net (code "53") (name "CFG_RESET") (class "Default")
      (node (ref "U$1") (pin "P16") (pinfunction "IO_L43N_GCLK22_IRDY2_3_P16") (pintype "bidirectional"))
      (node (ref "U3") (pin "36") (pinfunction "PB1_36") (pintype "bidirectional"))
    )
    (net (code "54") (name "CS_LLS") (class "Default")
      (node (ref "MICRO_SD1") (pin "2") (pinfunction "CD/DAT3_2") (pintype "bidirectional"))
      (node (ref "R21") (pin "2") (pinfunction "2_2") (pintype "passive"))
    )
    (net (code "55") (name "CTRL_CLK") (class "Default")
      (node (ref "U$1") (pin "P6") (pinfunction "IO_L52P_3_P6") (pintype "bidirectional"))
      (node (ref "U3") (pin "90") (pinfunction "PB4_90") (pintype "bidirectional"))
    )
    (net (code "56") (name "D0") (class "Default")
      (node (ref "4A") (pin "1") (pinfunction "P_1") (pintype "passive"))
      (node (ref "U$1") (pin "P23") (pinfunction "IO_L41N_GCLK26_3_P23") (pintype "bidirectional"))
      (node (ref "U2") (pin "13") (pinfunction "DQ0_13") (pintype "output"))
    )
    (net (code "57") (name "D1") (class "Default")
      (node (ref "5A") (pin "1") (pinfunction "P_1") (pintype "passive"))
      (node (ref "U$1") (pin "P26") (pinfunction "IO_L37N_3_P26") (pintype "bidirectional"))
      (node (ref "U2") (pin "14") (pinfunction "DQ1_14") (pintype "output"))
    )
    (net (code "58") (name "D2") (class "Default")
      (node (ref "6A") (pin "1") (pinfunction "P_1") (pintype "passive"))
      (node (ref "U$1") (pin "P27") (pinfunction "IO_L37P_3_P27") (pintype "bidirectional"))
      (node (ref "U2") (pin "15") (pinfunction "DQ2_15") (pintype "output"))
    )
    (net (code "59") (name "D3") (class "Default")
      (node (ref "9A") (pin "1") (pinfunction "P_1") (pintype "passive"))
      (node (ref "U$1") (pin "P34") (pinfunction "IO_L1N_VREF_3_P34") (pintype "bidirectional"))
      (node (ref "U2") (pin "17") (pinfunction "DQ3_17") (pintype "output"))
    )
    (net (code "60") (name "D4") (class "Default")
      (node (ref "10A") (pin "1") (pinfunction "P_1") (pintype "passive"))
      (node (ref "U$1") (pin "P39") (pinfunction "IO_L65P_INIT_B_2_P39") (pintype "bidirectional"))
      (node (ref "U2") (pin "18") (pinfunction "DQ4_18") (pintype "output"))
    )
    (net (code "61") (name "D5") (class "Default")
      (node (ref "8A") (pin "1") (pinfunction "P_1") (pintype "passive"))
      (node (ref "U$1") (pin "P32") (pinfunction "IO_L2N_3_P32") (pintype "bidirectional"))
      (node (ref "U2") (pin "19") (pinfunction "DQ5_19") (pintype "output"))
    )
    (net (code "62") (name "D6") (class "Default")
      (node (ref "7A") (pin "1") (pinfunction "P_1") (pintype "passive"))
      (node (ref "U$1") (pin "P29") (pinfunction "IO_L36N_3_P29") (pintype "bidirectional"))
      (node (ref "U2") (pin "20") (pinfunction "DQ6_20") (pintype "output"))
    )
    (net (code "63") (name "D7") (class "Default")
      (node (ref "1A") (pin "1") (pinfunction "P_1") (pintype "passive"))
      (node (ref "U$1") (pin "P21") (pinfunction "IO_L42N_GCLK24_3_P21") (pintype "bidirectional"))
      (node (ref "U2") (pin "21") (pinfunction "DQ7_21") (pintype "output"))
    )
    (net (code "64") (name "DI_LLS") (class "Default")
      (node (ref "MICRO_SD1") (pin "3") (pinfunction "CMD_3") (pintype "bidirectional"))
      (node (ref "R17") (pin "2") (pinfunction "2_2") (pintype "passive"))
    )
    (net (code "65") (name "DOWN") (class "Default")
      (node (ref "J2") (pin "2") (pinfunction "2_2") (pintype "passive"))
      (node (ref "U$1") (pin "P79") (pinfunction "IO_L47P_1_P79") (pintype "bidirectional"))
    )
    (net (code "66") (name "EN_M1_NOT") (class "Default")
      (node (ref "U$1") (pin "P140") (pinfunction "IO_L3P_0_P140") (pintype "bidirectional"))
      (node (ref "U3") (pin "25") (pinfunction "PA2_25") (pintype "bidirectional"))
    )
    (net (code "67") (name "FIRE") (class "Default")
      (node (ref "J2") (pin "6") (pinfunction "6_6") (pintype "passive"))
      (node (ref "U$1") (pin "P82") (pinfunction "IO_L45N_1_P82") (pintype "bidirectional"))
    )
    (net (code "68") (name "FLASH_CS") (class "Default")
      (node (ref "U$1") (pin "P38") (pinfunction "IO_L65N_CSO_B_2_P38") (pintype "bidirectional"))
      (node (ref "U4") (pin "1") (pinfunction "CS_1") (pintype "bidirectional"))
    )
    (net (code "69") (name "FLASH_MISO") (class "Default")
      (node (ref "U$1") (pin "P65") (pinfunction "IO_L3P_D0_DIN_MISO_MISO1_2_P65") (pintype "bidirectional"))
      (node (ref "U4") (pin "2") (pinfunction "MISO_2") (pintype "bidirectional"))
    )
    (net (code "70") (name "FLASH_MOSI") (class "Default")
      (node (ref "U$1") (pin "P64") (pinfunction "IO_L3N_MOSI_CSI_B_MISO0_2_P64") (pintype "bidirectional"))
      (node (ref "U4") (pin "5") (pinfunction "MOSI_5") (pintype "bidirectional"))
    )
    (net (code "71") (name "FLASH_SCLK") (class "Default")
      (node (ref "U$1") (pin "P70") (pinfunction "IO_L1P_CCLK_2_P70") (pintype "bidirectional"))
      (node (ref "U4") (pin "6") (pinfunction "SCK_6") (pintype "bidirectional"))
    )
    (net (code "72") (name "GET_CTRL_REG") (class "Default")
      (node (ref "U$1") (pin "P5") (pinfunction "IO_L52N_3_P5") (pintype "bidirectional"))
      (node (ref "U3") (pin "66") (pinfunction "PC9_66") (pintype "bidirectional"))
    )
    (net (code "73") (name "GET_DATA_REG") (class "Default")
      (node (ref "U$1") (pin "P2") (pinfunction "IO_L83P_3_P2") (pintype "bidirectional"))
      (node (ref "U3") (pin "78") (pinfunction "PC10_78") (pintype "bidirectional"))
    )
    (net (code "74") (name "GND") (class "Default")
      (node (ref "4B") (pin "1") (pinfunction "P_1") (pintype "passive"))
      (node (ref "5B") (pin "1") (pinfunction "P_1") (pintype "passive"))
      (node (ref "C1") (pin "2") (pinfunction "2_2") (pintype "passive"))
      (node (ref "C10") (pin "2") (pinfunction "2_2") (pintype "passive"))
      (node (ref "C11") (pin "1") (pinfunction "1_1") (pintype "passive"))
      (node (ref "C12") (pin "1") (pinfunction "1_1") (pintype "passive"))
      (node (ref "C18") (pin "2") (pinfunction "2_2") (pintype "passive"))
      (node (ref "C19") (pin "2") (pinfunction "2_2") (pintype "passive"))
      (node (ref "C2") (pin "2") (pinfunction "2_2") (pintype "passive"))
      (node (ref "C22") (pin "1") (pinfunction "1_1") (pintype "passive"))
      (node (ref "C23") (pin "1") (pinfunction "1_1") (pintype "passive"))
      (node (ref "C24") (pin "2") (pinfunction "2_2") (pintype "passive"))
      (node (ref "C25") (pin "2") (pinfunction "2_2") (pintype "passive"))
      (node (ref "C26") (pin "2") (pinfunction "2_2") (pintype "passive"))
      (node (ref "C3") (pin "2") (pinfunction "2_2") (pintype "passive"))
      (node (ref "C33") (pin "2") (pinfunction "2_2") (pintype "passive"))
      (node (ref "C4") (pin "1") (pinfunction "1_1") (pintype "passive"))
      (node (ref "C5") (pin "1") (pinfunction "1_1") (pintype "passive"))
      (node (ref "C7") (pin "2") (pinfunction "2_2") (pintype "passive"))
      (node (ref "IC10") (pin "2") (pinfunction "VSS_2") (pintype "passive"))
      (node (ref "IC10") (pin "6") (pinfunction "A0_6") (pintype "passive"))
      (node (ref "IC2") (pin "1") (pinfunction "GND_1") (pintype "power_in"))
      (node (ref "IC5") (pin "1") (pinfunction "GND_1") (pintype "power_in"))
      (node (ref "J2") (pin "8") (pinfunction "8_8") (pintype "passive"))
      (node (ref "J3") (pin "A1_B12") (pinfunction "GND_A1_B12") (pintype "power_in"))
      (node (ref "J3") (pin "B1_A12") (pinfunction "GND_B1_A12") (pintype "power_in"))
      (node (ref "J3") (pin "SH1") (pinfunction "SHIELD_SH1") (pintype "passive"))
      (node (ref "J3") (pin "SH2") (pinfunction "SHIELD_SH2") (pintype "passive"))
      (node (ref "J3") (pin "SH3") (pinfunction "SHIELD_SH3") (pintype "passive"))
      (node (ref "J3") (pin "SH4") (pinfunction "SHIELD_SH4") (pintype "passive"))
      (node (ref "JP1") (pin "1") (pinfunction "1_1") (pintype "passive"))
      (node (ref "JP2") (pin "2") (pinfunction "2_2") (pintype "passive"))
      (node (ref "JP4") (pin "2") (pinfunction "2_2") (pintype "passive"))
      (node (ref "JP8") (pin "2") (pinfunction "2_2") (pintype "passive"))
      (node (ref "LED3") (pin "P1") (pinfunction "C_P1") (pintype "passive"))
      (node (ref "LED3") (pin "P2") (pinfunction "C_P2") (pintype "passive"))
      (node (ref "LED3") (pin "P3") (pinfunction "C_P3") (pintype "passive"))
      (node (ref "MICRO_SD1") (pin "6") (pinfunction "VSS_6") (pintype "power_in"))
      (node (ref "MICRO_SD1") (pin "MP1") (pinfunction "SHIELD_MP1") (pintype "power_in"))
      (node (ref "MICRO_SD1") (pin "MP2") (pinfunction "SHIELD_MP2") (pintype "power_in"))
      (node (ref "MICRO_SD1") (pin "MP3") (pinfunction "SHIELD_MP3") (pintype "power_in"))
      (node (ref "MICRO_SD1") (pin "MP4") (pinfunction "SHIELD_MP4") (pintype "power_in"))
      (node (ref "R25") (pin "1") (pinfunction "1_1") (pintype "passive"))
      (node (ref "R30") (pin "1") (pinfunction "1_1") (pintype "passive"))
      (node (ref "S1") (pin "1") (pinfunction "P_1") (pintype "passive"))
      (node (ref "U$1") (pin "P108") (pinfunction "GND_P108") (pintype "bidirectional"))
      (node (ref "U$1") (pin "P113") (pinfunction "GND_P113") (pintype "bidirectional"))
      (node (ref "U$1") (pin "P13") (pinfunction "GND_P13") (pintype "bidirectional"))
      (node (ref "U$1") (pin "P130") (pinfunction "GND_P130") (pintype "bidirectional"))
      (node (ref "U$1") (pin "P136") (pinfunction "GND_P136") (pintype "bidirectional"))
      (node (ref "U$1") (pin "P25") (pinfunction "GND_P25") (pintype "bidirectional"))
      (node (ref "U$1") (pin "P3") (pinfunction "GND_P3") (pintype "bidirectional"))
      (node (ref "U$1") (pin "P49") (pinfunction "GND_P49") (pintype "bidirectional"))
      (node (ref "U$1") (pin "P54") (pinfunction "GND_P54") (pintype "bidirectional"))
      (node (ref "U$1") (pin "P68") (pinfunction "GND_P68") (pintype "bidirectional"))
      (node (ref "U$1") (pin "P73") (pinfunction "SUSPEND_P73") (pintype "bidirectional"))
      (node (ref "U$1") (pin "P77") (pinfunction "GND_P77") (pintype "bidirectional"))
      (node (ref "U$1") (pin "P91") (pinfunction "GND_P91") (pintype "bidirectional"))
      (node (ref "U$1") (pin "P96") (pinfunction "GND_P96") (pintype "bidirectional"))
      (node (ref "U2") (pin "16") (pinfunction "VSS_16") (pintype "output"))
      (node (ref "U3") (pin "10") (pinfunction "VSS_10") (pintype "bidirectional"))
      (node (ref "U3") (pin "20") (pinfunction "VSSA_20") (pintype "bidirectional"))
      (node (ref "U3") (pin "27") (pinfunction "VSS_27") (pintype "bidirectional"))
      (node (ref "U3") (pin "74") (pinfunction "VSS_74") (pintype "bidirectional"))
      (node (ref "U3") (pin "99") (pinfunction "VSS_99") (pintype "bidirectional"))
      (node (ref "U4") (pin "4") (pinfunction "GND_4") (pintype "bidirectional"))
    )
    (net (code "75") (name "LEDB") (class "Default")
      (node (ref "R3") (pin "1") (pinfunction "1_1") (pintype "passive"))
      (node (ref "U3") (pin "79") (pinfunction "PC11_79") (pintype "bidirectional"))
    )
    (net (code "76") (name "LEDG") (class "Default")
      (node (ref "R13") (pin "1") (pinfunction "1_1") (pintype "passive"))
      (node (ref "U3") (pin "17") (pinfunction "PC2_17") (pintype "bidirectional"))
    )
    (net (code "77") (name "LEDR") (class "Default")
      (node (ref "R2") (pin "1") (pinfunction "1_1") (pintype "passive"))
      (node (ref "U3") (pin "80") (pinfunction "PC12_80") (pintype "bidirectional"))
    )
    (net (code "78") (name "LEFT") (class "Default")
      (node (ref "J2") (pin "3") (pinfunction "3_3") (pintype "passive"))
      (node (ref "U$1") (pin "P80") (pinfunction "IO_L46N_1_P80") (pintype "bidirectional"))
    )
    (net (code "79") (name "LE_IL") (class "Default")
      (node (ref "U$1") (pin "P14") (pinfunction "IO_L44N_GCLK20_3_P14") (pintype "bidirectional"))
      (node (ref "U3") (pin "7") (pinfunction "PC13_7") (pintype "bidirectional"))
    )
    (net (code "80") (name "MEM_ACCESS") (class "Default")
      (node (ref "U$1") (pin "P11") (pinfunction "IO_L49N_3_P11") (pintype "bidirectional"))
      (node (ref "U3") (pin "16") (pinfunction "PC1_16") (pintype "bidirectional"))
    )
    (net (code "81") (name "MISO") (class "Default")
      (node (ref "R20") (pin "1") (pinfunction "1_1") (pintype "passive"))
      (node (ref "U3") (pin "31") (pinfunction "PA6_31") (pintype "bidirectional"))
    )
    (net (code "82") (name "MOSI") (class "Default")
      (node (ref "R17") (pin "1") (pinfunction "1_1") (pintype "passive"))
      (node (ref "U3") (pin "32") (pinfunction "PA7_32") (pintype "bidirectional"))
    )
    (net (code "83") (name "Net-(J3-DN1)") (class "Default")
      (node (ref "J3") (pin "A7") (pinfunction "DN1_A7") (pintype "bidirectional"))
      (node (ref "J3") (pin "B7") (pinfunction "DN2_B7") (pintype "bidirectional"))
      (node (ref "R26") (pin "1") (pinfunction "1_1") (pintype "passive"))
    )
    (net (code "84") (name "Net-(J3-DP1)") (class "Default")
      (node (ref "J3") (pin "A6") (pinfunction "DP1_A6") (pintype "bidirectional"))
      (node (ref "J3") (pin "B6") (pinfunction "DP2_B6") (pintype "bidirectional"))
      (node (ref "R22") (pin "1") (pinfunction "1_1") (pintype "passive"))
      (node (ref "R23") (pin "1") (pinfunction "1_1") (pintype "passive"))
    )
    (net (code "85") (name "Net-(JP7-Pad1)") (class "Default")
      (node (ref "JP7") (pin "1") (pinfunction "1_1") (pintype "passive"))
      (node (ref "R24") (pin "2") (pinfunction "2_2") (pintype "passive"))
    )
    (net (code "86") (name "Net-(JP7-Pad3)") (class "Default")
      (node (ref "JP7") (pin "3") (pinfunction "3_3") (pintype "passive"))
      (node (ref "R16") (pin "1") (pinfunction "1_1") (pintype "passive"))
    )
    (net (code "87") (name "Net-(LED2-PadA)") (class "Default")
      (node (ref "LED2") (pin "A") (pinfunction "A_A") (pintype "passive"))
      (node (ref "R11") (pin "2") (pinfunction "2_2") (pintype "passive"))
    )
    (net (code "88") (name "Net-(LED3A-A)") (class "Default")
      (node (ref "LED3") (pin "P6") (pinfunction "A_P6") (pintype "passive"))
      (node (ref "R3") (pin "2") (pinfunction "2_2") (pintype "passive"))
    )
    (net (code "89") (name "Net-(LED3B-A)") (class "Default")
      (node (ref "LED3") (pin "P5") (pinfunction "A_P5") (pintype "passive"))
      (node (ref "R13") (pin "2") (pinfunction "2_2") (pintype "passive"))
    )
    (net (code "90") (name "Net-(LED3C-A)") (class "Default")
      (node (ref "LED3") (pin "P4") (pinfunction "A_P4") (pintype "passive"))
      (node (ref "R2") (pin "2") (pinfunction "2_2") (pintype "passive"))
    )
    (net (code "91") (name "Net-(MICRO_SD1-DAT0)") (class "Default")
      (node (ref "MICRO_SD1") (pin "7") (pinfunction "DAT0_7") (pintype "bidirectional"))
      (node (ref "R20") (pin "2") (pinfunction "2_2") (pintype "passive"))
    )
    (net (code "92") (name "Net-(Q3-2)") (class "Default")
      (node (ref "C12") (pin "2") (pinfunction "2_2") (pintype "passive"))
      (node (ref "Q3") (pin "3") (pinfunction "2_3") (pintype "passive"))
      (node (ref "R14") (pin "2") (pinfunction "2_2") (pintype "passive"))
      (node (ref "U3") (pin "13") (pinfunction "PH1_13") (pintype "bidirectional"))
    )
    (net (code "93") (name "Net-(U$1-IO_L49P_D3_2)") (class "Default")
      (node (ref "SJ2") (pin "1") (pinfunction "1_1") (pintype "passive"))
      (node (ref "U$1") (pin "P46") (pinfunction "IO_L49P_D3_2_P46") (pintype "bidirectional"))
    )
    (net (code "94") (name "Net-(U$1-PROGRAM_B_2)") (class "Default")
      (node (ref "R12") (pin "2") (pinfunction "2_2") (pintype "passive"))
      (node (ref "U$1") (pin "P37") (pinfunction "PROGRAM_B_2_P37") (pintype "bidirectional"))
    )
    (net (code "95") (name "Net-(U3-PC14)") (class "Default")
      (node (ref "C22") (pin "2") (pinfunction "2_2") (pintype "passive"))
      (node (ref "Q4") (pin "2") (pinfunction "2_2") (pintype "passive"))
      (node (ref "U3") (pin "8") (pinfunction "PC14_8") (pintype "bidirectional"))
    )
    (net (code "96") (name "Net-(U3-PC15)") (class "Default")
      (node (ref "C23") (pin "2") (pinfunction "2_2") (pintype "passive"))
      (node (ref "Q4") (pin "1") (pinfunction "1_1") (pintype "passive"))
      (node (ref "U3") (pin "9") (pinfunction "PC15_9") (pintype "bidirectional"))
    )
    (net (code "97") (name "Net-(U3-PH0)") (class "Default")
      (node (ref "C11") (pin "2") (pinfunction "2_2") (pintype "passive"))
      (node (ref "Q3") (pin "1") (pinfunction "1_1") (pintype "passive"))
      (node (ref "R14") (pin "1") (pinfunction "1_1") (pintype "passive"))
      (node (ref "U3") (pin "12") (pinfunction "PH0_12") (pintype "bidirectional"))
    )
    (net (code "98") (name "Net-(U3-VCAP_1)") (class "Default")
      (node (ref "C10") (pin "1") (pinfunction "1_1") (pintype "passive"))
      (node (ref "U3") (pin "49") (pinfunction "VCAP_1_49") (pintype "bidirectional"))
    )
    (net (code "99") (name "Net-(U3-VCAP_2)") (class "Default")
      (node (ref "C7") (pin "1") (pinfunction "1_1") (pintype "passive"))
      (node (ref "U3") (pin "73") (pinfunction "VCAP_2_73") (pintype "bidirectional"))
    )
    (net (code "100") (name "O0") (class "Default")
      (node (ref "U$1") (pin "P126") (pinfunction "IO_L36N_GCLK14_0_P126") (pintype "bidirectional"))
      (node (ref "U3") (pin "81") (pinfunction "PD0_81") (pintype "bidirectional"))
    )
    (net (code "101") (name "O1") (class "Default")
      (node (ref "U$1") (pin "P127") (pinfunction "IO_L36P_GCLK15_0_P127") (pintype "bidirectional"))
      (node (ref "U3") (pin "82") (pinfunction "PD1_82") (pintype "bidirectional"))
    )
    (net (code "102") (name "O2") (class "Default")
      (node (ref "U$1") (pin "P131") (pinfunction "IO_L35N_GCLK16_0_P131") (pintype "bidirectional"))
      (node (ref "U3") (pin "83") (pinfunction "PD2_83") (pintype "bidirectional"))
    )
    (net (code "103") (name "O3") (class "Default")
      (node (ref "U$1") (pin "P132") (pinfunction "IO_L35P_GCLK17_0_P132") (pintype "bidirectional"))
      (node (ref "U3") (pin "84") (pinfunction "PD3_84") (pintype "bidirectional"))
    )
    (net (code "104") (name "O4") (class "Default")
      (node (ref "U$1") (pin "P133") (pinfunction "IO_L34N_GCLK18_0_P133") (pintype "bidirectional"))
      (node (ref "U3") (pin "85") (pinfunction "PD4_85") (pintype "bidirectional"))
    )
    (net (code "105") (name "O5") (class "Default")
      (node (ref "U$1") (pin "P134") (pinfunction "IO_L34P_GCLK19_0_P134") (pintype "bidirectional"))
      (node (ref "U3") (pin "86") (pinfunction "PD5_86") (pintype "bidirectional"))
    )
    (net (code "106") (name "O6") (class "Default")
      (node (ref "U$1") (pin "P137") (pinfunction "IO_L4N_0_P137") (pintype "bidirectional"))
      (node (ref "U3") (pin "87") (pinfunction "PD6_87") (pintype "bidirectional"))
    )
    (net (code "107") (name "O7") (class "Default")
      (node (ref "U$1") (pin "P138") (pinfunction "IO_L4P_0_P138") (pintype "bidirectional"))
      (node (ref "U3") (pin "88") (pinfunction "PD7_88") (pintype "bidirectional"))
    )
    (net (code "108") (name "PA11{slash}USB_DN") (class "Default")
      (node (ref "R26") (pin "2") (pinfunction "2_2") (pintype "passive"))
      (node (ref "U3") (pin "70") (pinfunction "PA11_70") (pintype "bidirectional"))
    )
    (net (code "109") (name "PA12{slash}USB_DP") (class "Default")
      (node (ref "R23") (pin "2") (pinfunction "2_2") (pintype "passive"))
      (node (ref "U3") (pin "71") (pinfunction "PA12_71") (pintype "bidirectional"))
    )
    (net (code "110") (name "PA13{slash}JTMS{slash}SWDIO") (class "Default")
      (node (ref "JP8") (pin "1") (pinfunction "1_1") (pintype "passive"))
      (node (ref "U3") (pin "72") (pinfunction "PA13_72") (pintype "bidirectional"))
    )
    (net (code "111") (name "PA14{slash}JTCK{slash}SWCLK") (class "Default")
      (node (ref "JP8") (pin "3") (pinfunction "3_3") (pintype "passive"))
      (node (ref "U3") (pin "76") (pinfunction "PA14_76") (pintype "bidirectional"))
    )
    (net (code "112") (name "PAGE_A8") (class "Default")
      (node (ref "U$1") (pin "P143") (pinfunction "IO_L1N_VREF_0_P143") (pintype "bidirectional"))
      (node (ref "U3") (pin "24") (pinfunction "PA1_24") (pintype "bidirectional"))
    )
    (net (code "113") (name "PB2{slash}BOOT1") (class "Default")
      (node (ref "R16") (pin "2") (pinfunction "2_2") (pintype "passive"))
      (node (ref "R25") (pin "2") (pinfunction "2_2") (pintype "passive"))
      (node (ref "U3") (pin "37") (pinfunction "PB2_37") (pintype "bidirectional"))
    )
    (net (code "114") (name "RESET") (class "Default")
      (node (ref "C5") (pin "2") (pinfunction "2_2") (pintype "passive"))
      (node (ref "D1") (pin "A") (pinfunction "A_A") (pintype "passive"))
      (node (ref "R15") (pin "1") (pinfunction "1_1") (pintype "passive"))
      (node (ref "S1") (pin "2") (pinfunction "S_2") (pintype "passive"))
      (node (ref "U3") (pin "14") (pinfunction "NRST_14") (pintype "bidirectional"))
    )
    (net (code "115") (name "RIGHT") (class "Default")
      (node (ref "J2") (pin "4") (pinfunction "4_4") (pintype "passive"))
      (node (ref "U$1") (pin "P81") (pinfunction "IO_L46P_1_P81") (pintype "bidirectional"))
    )
    (net (code "116") (name "ROM_WR_EN") (class "Default")
      (node (ref "U$1") (pin "P142") (pinfunction "IO_L2P_0_P142") (pintype "bidirectional"))
      (node (ref "U3") (pin "67") (pinfunction "PA8_67") (pintype "bidirectional"))
    )
    (net (code "117") (name "RST_CTRL_REG") (class "Default")
      (node (ref "U$1") (pin "P1") (pinfunction "IO_L83N_VREF_3_P1") (pintype "bidirectional"))
      (node (ref "U3") (pin "53") (pinfunction "PB14_53") (pintype "bidirectional"))
    )
    (net (code "118") (name "RST_DATA_REG") (class "Default")
      (node (ref "U$1") (pin "P144") (pinfunction "IO_L1P_HSWAPEN_0_P144") (pintype "bidirectional"))
      (node (ref "U3") (pin "91") (pinfunction "PB5_91") (pintype "bidirectional"))
    )
    (net (code "119") (name "SCK_LLS") (class "Default")
      (node (ref "MICRO_SD1") (pin "5") (pinfunction "CLK_5") (pintype "bidirectional"))
      (node (ref "R18") (pin "2") (pinfunction "2_2") (pintype "passive"))
    )
    (net (code "120") (name "SCL") (class "Default")
      (node (ref "IC10") (pin "5") (pinfunction "SCL_5") (pintype "passive"))
      (node (ref "U3") (pin "92") (pinfunction "PB6_92") (pintype "bidirectional"))
    )
    (net (code "121") (name "SCLK") (class "Default")
      (node (ref "R18") (pin "1") (pinfunction "1_1") (pintype "passive"))
      (node (ref "U3") (pin "30") (pinfunction "PA5_30") (pintype "bidirectional"))
    )
    (net (code "122") (name "SDA") (class "Default")
      (node (ref "IC10") (pin "4") (pinfunction "SDA_4") (pintype "passive"))
      (node (ref "U3") (pin "93") (pinfunction "PB7_93") (pintype "bidirectional"))
    )
    (net (code "123") (name "SD_LED") (class "Default")
      (node (ref "LED2") (pin "C") (pinfunction "C_C") (pintype "passive"))
      (node (ref "U3") (pin "29") (pinfunction "PA4_29") (pintype "bidirectional"))
    )
    (net (code "124") (name "SEL_128CHARS") (class "Default")
      (node (ref "U$1") (pin "P141") (pinfunction "IO_L2N_0_P141") (pintype "bidirectional"))
      (node (ref "U3") (pin "77") (pinfunction "PA15_77") (pintype "bidirectional"))
    )
    (net (code "125") (name "SPARE1") (class "Default")
      (node (ref "JP5") (pin "4") (pinfunction "4_4") (pintype "passive"))
      (node (ref "U$1") (pin "P7") (pinfunction "IO_L51N_3_P7") (pintype "bidirectional"))
      (node (ref "U3") (pin "18") (pinfunction "PC3_18") (pintype "bidirectional"))
    )
    (net (code "126") (name "SPARE2") (class "Default")
      (node (ref "JP5") (pin "3") (pinfunction "3_3") (pintype "passive"))
      (node (ref "U$1") (pin "P8") (pinfunction "IO_L51P_3_P8") (pintype "bidirectional"))
      (node (ref "U3") (pin "33") (pinfunction "PC4_33") (pintype "bidirectional"))
    )
    (net (code "127") (name "SPARE3") (class "Default")
      (node (ref "JP5") (pin "2") (pinfunction "2_2") (pintype "passive"))
      (node (ref "U$1") (pin "P9") (pinfunction "IO_L50N_3_P9") (pintype "bidirectional"))
      (node (ref "U3") (pin "34") (pinfunction "PC5_34") (pintype "bidirectional"))
    )
    (net (code "128") (name "SPARE4") (class "Default")
      (node (ref "JP5") (pin "1") (pinfunction "1_1") (pintype "passive"))
      (node (ref "U$1") (pin "P10") (pinfunction "IO_L50P_3_P10") (pintype "bidirectional"))
      (node (ref "U3") (pin "63") (pinfunction "PC6_63") (pintype "bidirectional"))
    )
    (net (code "129") (name "SPEAKER") (class "Default")
      (node (ref "IC10") (pin "1") (pinfunction "VOUT_1") (pintype "passive"))
      (node (ref "JP1") (pin "2") (pinfunction "2_2") (pintype "passive"))
    )
    (net (code "130") (name "SS_SD") (class "Default")
      (node (ref "R21") (pin "1") (pinfunction "1_1") (pintype "passive"))
      (node (ref "U3") (pin "54") (pinfunction "PB15_54") (pintype "bidirectional"))
    )
    (net (code "131") (name "TCK") (class "Default")
      (node (ref "JP3") (pin "1") (pinfunction "1_1") (pintype "passive"))
      (node (ref "U$1") (pin "P109") (pinfunction "TCK_P109") (pintype "bidirectional"))
    )
    (net (code "132") (name "TDI") (class "Default")
      (node (ref "JP3") (pin "3") (pinfunction "3_3") (pintype "passive"))
      (node (ref "U$1") (pin "P110") (pinfunction "TDI_P110") (pintype "bidirectional"))
    )
    (net (code "133") (name "TDO") (class "Default")
      (node (ref "JP3") (pin "2") (pinfunction "2_2") (pintype "passive"))
      (node (ref "U$1") (pin "P106") (pinfunction "TDO_P106") (pintype "bidirectional"))
    )
    (net (code "134") (name "TMS") (class "Default")
      (node (ref "JP3") (pin "4") (pinfunction "4_4") (pintype "passive"))
      (node (ref "U$1") (pin "P107") (pinfunction "TMS_P107") (pintype "bidirectional"))
    )
    (net (code "135") (name "UART_RX") (class "Default")
      (node (ref "JP4") (pin "3") (pinfunction "3_3") (pintype "passive"))
      (node (ref "U3") (pin "69") (pinfunction "PA10_69") (pintype "bidirectional"))
    )
    (net (code "136") (name "UART_TX") (class "Default")
      (node (ref "JP4") (pin "4") (pinfunction "4_4") (pintype "passive"))
      (node (ref "U3") (pin "68") (pinfunction "PA9_68") (pintype "bidirectional"))
    )
    (net (code "137") (name "UP") (class "Default")
      (node (ref "J2") (pin "1") (pinfunction "1_1") (pintype "passive"))
      (node (ref "U$1") (pin "P78") (pinfunction "IO_L47N_1_P78") (pintype "bidirectional"))
    )
    (net (code "138") (name "VCC") (class "Default")
      (node (ref "1B") (pin "1") (pinfunction "P_1") (pintype "passive"))
      (node (ref "C1") (pin "1") (pinfunction "1_1") (pintype "passive"))
      (node (ref "C19") (pin "1") (pinfunction "1_1") (pintype "passive"))
      (node (ref "C2") (pin "1") (pinfunction "1_1") (pintype "passive"))
      (node (ref "C3") (pin "1") (pinfunction "1_1") (pintype "passive"))
      (node (ref "D1") (pin "C") (pinfunction "C_C") (pintype "passive"))
      (node (ref "IC10") (pin "3") (pinfunction "VDD_3") (pintype "passive"))
      (node (ref "IC2") (pin "3") (pinfunction "VIN_3") (pintype "input"))
      (node (ref "IC5") (pin "3") (pinfunction "VIN_3") (pintype "input"))
      (node (ref "JP4") (pin "1") (pinfunction "1_1") (pintype "passive"))
      (node (ref "JP6") (pin "2") (pinfunction "2_2") (pintype "passive"))
      (node (ref "R11") (pin "1") (pinfunction "1_1") (pintype "passive"))
      (node (ref "R15") (pin "2") (pinfunction "2_2") (pintype "passive"))
      (node (ref "R22") (pin "2") (pinfunction "2_2") (pintype "passive"))
      (node (ref "U2") (pin "32") (pinfunction "VCC_32") (pintype "power_in"))
    )
    (net (code "139") (name "VCC_USB") (class "Default")
      (node (ref "J3") (pin "A4_B9") (pinfunction "VBUS_A4_B9") (pintype "power_in"))
      (node (ref "J3") (pin "B4_A9") (pinfunction "VBUS_B4_A9") (pintype "power_in"))
      (node (ref "JP6") (pin "1") (pinfunction "1_1") (pintype "passive"))
    )
    (net (code "140") (name "unconnected-(J2-Pad5)") (class "Default")
      (node (ref "J2") (pin "5") (pinfunction "5_5") (pintype "passive"))
    )
    (net (code "141") (name "unconnected-(J2-Pad7)") (class "Default")
      (node (ref "J2") (pin "7") (pinfunction "7_7") (pintype "passive"))
    )
    (net (code "142") (name "unconnected-(J2-Pad9)") (class "Default")
      (node (ref "J2") (pin "9") (pinfunction "9_9") (pintype "passive"))
    )
    (net (code "143") (name "unconnected-(MICRO_SD1-CD-PadCD1)") (class "Default")
      (node (ref "MICRO_SD1") (pin "CD1") (pinfunction "CD_CD1") (pintype "passive"))
    )
    (net (code "144") (name "unconnected-(MICRO_SD1-DAT1-Pad8)") (class "Default")
      (node (ref "MICRO_SD1") (pin "8") (pinfunction "DAT1_8") (pintype "bidirectional"))
    )
    (net (code "145") (name "unconnected-(MICRO_SD1-DAT2-Pad1)") (class "Default")
      (node (ref "MICRO_SD1") (pin "1") (pinfunction "DAT2_1") (pintype "bidirectional"))
    )
    (net (code "146") (name "unconnected-(U$1-CMPCS_B_2-PadP72)") (class "Default")
      (node (ref "U$1") (pin "P72") (pinfunction "CMPCS_B_2_P72") (pintype "bidirectional"))
    )
    (net (code "147") (name "unconnected-(U$1-DONE_2-PadP71)") (class "Default")
      (node (ref "U$1") (pin "P71") (pinfunction "DONE_2_P71") (pintype "bidirectional"))
    )
    (net (code "148") (name "unconnected-(U3-PA3-Pad26)") (class "Default")
      (node (ref "U3") (pin "26") (pinfunction "PA3_26") (pintype "bidirectional"))
    )
    (net (code "149") (name "unconnected-(U3-PB8-Pad95)") (class "Default")
      (node (ref "U3") (pin "95") (pinfunction "PB8_95") (pintype "bidirectional"))
    )
    (net (code "150") (name "unconnected-(U3-PC7-Pad64)") (class "Default")
      (node (ref "U3") (pin "64") (pinfunction "PC7_64") (pintype "bidirectional"))
    )
    (net (code "151") (name "unconnected-(U3-PC8-Pad65)") (class "Default")
      (node (ref "U3") (pin "65") (pinfunction "PC8_65") (pintype "bidirectional"))
    )
    (net (code "152") (name "{slash}BUSAK") (class "Default")
      (node (ref "18A") (pin "1") (pinfunction "P_1") (pintype "passive"))
    )
    (net (code "153") (name "{slash}BUSRQ") (class "Default")
      (node (ref "20A") (pin "1") (pinfunction "P_1") (pintype "passive"))
    )
    (net (code "154") (name "{slash}CLOCK") (class "Default")
      (node (ref "6B") (pin "1") (pinfunction "P_1") (pintype "passive"))
      (node (ref "U$1") (pin "P24") (pinfunction "IO_L41P_GCLK27_3_P24") (pintype "bidirectional"))
    )
    (net (code "155") (name "{slash}HALT") (class "Default")
      (node (ref "13A") (pin "1") (pinfunction "P_1") (pintype "passive"))
      (node (ref "SJ2") (pin "2") (pinfunction "2_2") (pintype "passive"))
    )
    (net (code "156") (name "{slash}IORQ") (class "Default")
      (node (ref "15A") (pin "1") (pinfunction "P_1") (pintype "passive"))
      (node (ref "U$1") (pin "P51") (pinfunction "IO_L31P_GCLK31_D14_2_P51") (pintype "bidirectional"))
    )
    (net (code "157") (name "{slash}M1") (class "Default")
      (node (ref "22A") (pin "1") (pinfunction "P_1") (pintype "passive"))
      (node (ref "U$1") (pin "P67") (pinfunction "IO_L2P_CMPCLK_2_P67") (pintype "bidirectional"))
    )
    (net (code "158") (name "{slash}MEM_CE") (class "Default")
      (node (ref "U$1") (pin "P85") (pinfunction "IO_L43P_GCLK5_1_P85") (pintype "bidirectional"))
      (node (ref "U2") (pin "22") (pinfunction "CE_22") (pintype "input"))
    )
    (net (code "159") (name "{slash}MEM_OE") (class "Default")
      (node (ref "U$1") (pin "P92") (pinfunction "IO_L41N_GCLK8_1_P92") (pintype "bidirectional"))
      (node (ref "U2") (pin "24") (pinfunction "OE_24") (pintype "input"))
    )
    (net (code "160") (name "{slash}MREQ") (class "Default")
      (node (ref "14A") (pin "1") (pinfunction "P_1") (pintype "passive"))
      (node (ref "U$1") (pin "P48") (pinfunction "IO_L48P_D7_2_P48") (pintype "bidirectional"))
    )
    (net (code "161") (name "{slash}NMI") (class "Default")
      (node (ref "12A") (pin "1") (pinfunction "P_1") (pintype "passive"))
      (node (ref "U$1") (pin "P44") (pinfunction "IO_L62P_D5_2_P44") (pintype "bidirectional"))
    )
    (net (code "162") (name "{slash}OE_OL") (class "Default")
      (node (ref "U$1") (pin "P12") (pinfunction "IO_L49P_3_P12") (pintype "bidirectional"))
      (node (ref "U3") (pin "47") (pinfunction "PB10_47") (pintype "bidirectional"))
    )
    (net (code "163") (name "{slash}RAMCS") (class "Default")
      (node (ref "2A") (pin "1") (pinfunction "P_1") (pintype "passive"))
      (node (ref "U$1") (pin "P22") (pinfunction "IO_L42P_GCLK25_TRDY2_3_P22") (pintype "bidirectional"))
    )
    (net (code "164") (name "{slash}RD") (class "Default")
      (node (ref "16A") (pin "1") (pinfunction "P_1") (pintype "passive"))
      (node (ref "U$1") (pin "P56") (pinfunction "IO_L30P_GCLK1_D13_2_P56") (pintype "bidirectional"))
    )
    (net (code "165") (name "{slash}RESET") (class "Default")
      (node (ref "21A") (pin "1") (pinfunction "P_1") (pintype "passive"))
      (node (ref "U$1") (pin "P139") (pinfunction "IO_L3N_0_P139") (pintype "bidirectional"))
      (node (ref "U3") (pin "96") (pinfunction "PB9_96") (pintype "bidirectional"))
    )
    (net (code "166") (name "{slash}RFSH") (class "Default")
      (node (ref "23A") (pin "1") (pinfunction "P_1") (pintype "passive"))
      (node (ref "U$1") (pin "P74") (pinfunction "IO_L74N_DOUT_BUSY_1_P74") (pintype "bidirectional"))
    )
    (net (code "167") (name "{slash}ROMCS") (class "Default")
      (node (ref "23B") (pin "1") (pinfunction "P_1") (pintype "passive"))
      (node (ref "U$1") (pin "P75") (pinfunction "IO_L74P_AWAKE_1_P75") (pintype "bidirectional"))
    )
    (net (code "168") (name "{slash}WAIT") (class "Default")
      (node (ref "19A") (pin "1") (pinfunction "P_1") (pintype "passive"))
      (node (ref "U$1") (pin "P61") (pinfunction "IO_L12N_D2_MISO3_2_P61") (pintype "bidirectional"))
      (node (ref "U3") (pin "23") (pinfunction "PA0_23") (pintype "bidirectional"))
    )
    (net (code "169") (name "{slash}WR") (class "Default")
      (node (ref "17A") (pin "1") (pinfunction "P_1") (pintype "passive"))
      (node (ref "U$1") (pin "P58") (pinfunction "IO_L14P_D11_2_P58") (pintype "bidirectional"))
      (node (ref "U3") (pin "15") (pinfunction "PC0_15") (pintype "bidirectional"))
    )
    (net (code "170") (name "{slash}WR'") (class "Default")
      (node (ref "U$1") (pin "P102") (pinfunction "IO_L32P_1_P102") (pintype "bidirectional"))
      (node (ref "U2") (pin "29") (pinfunction "WE_29") (pintype "input"))
    )
  )
)
